# PCB-CMB-5-SHLD-1208.net
KiCad netlist of a schematic drawn in EAGLE
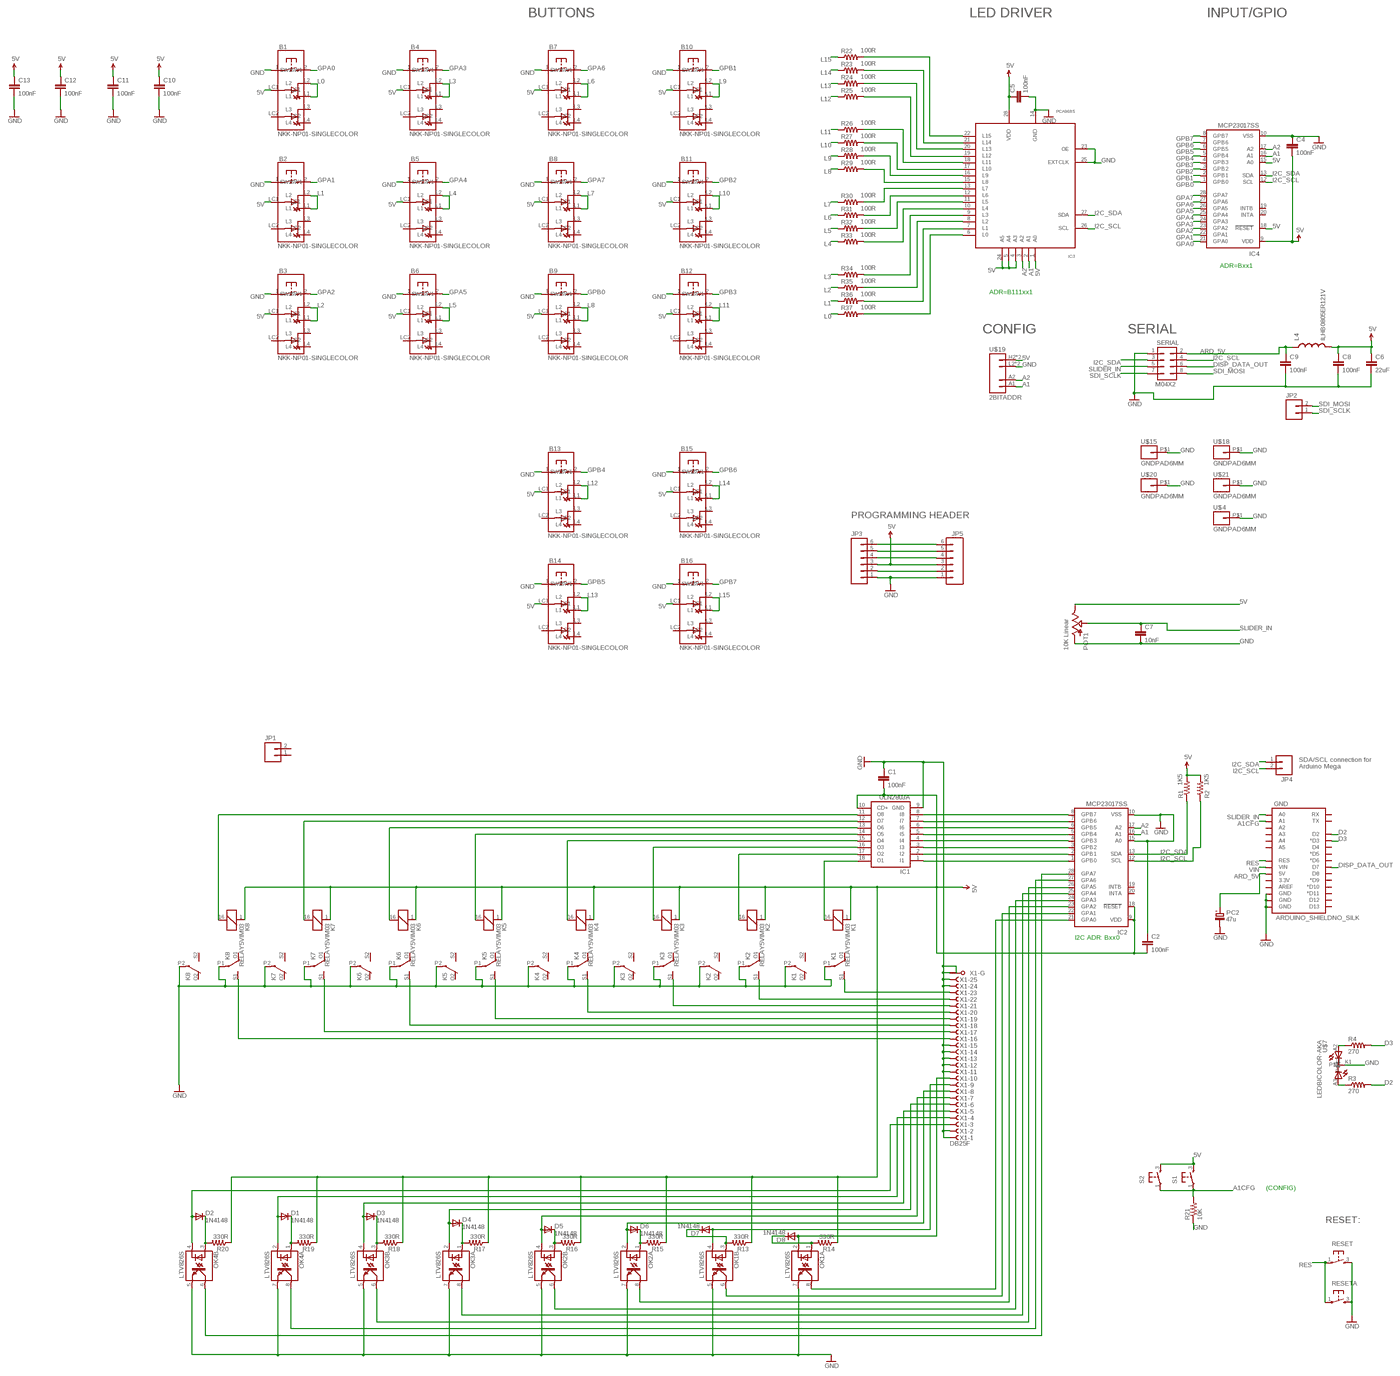
[diagram p0: schematic, sheet 1, overview]
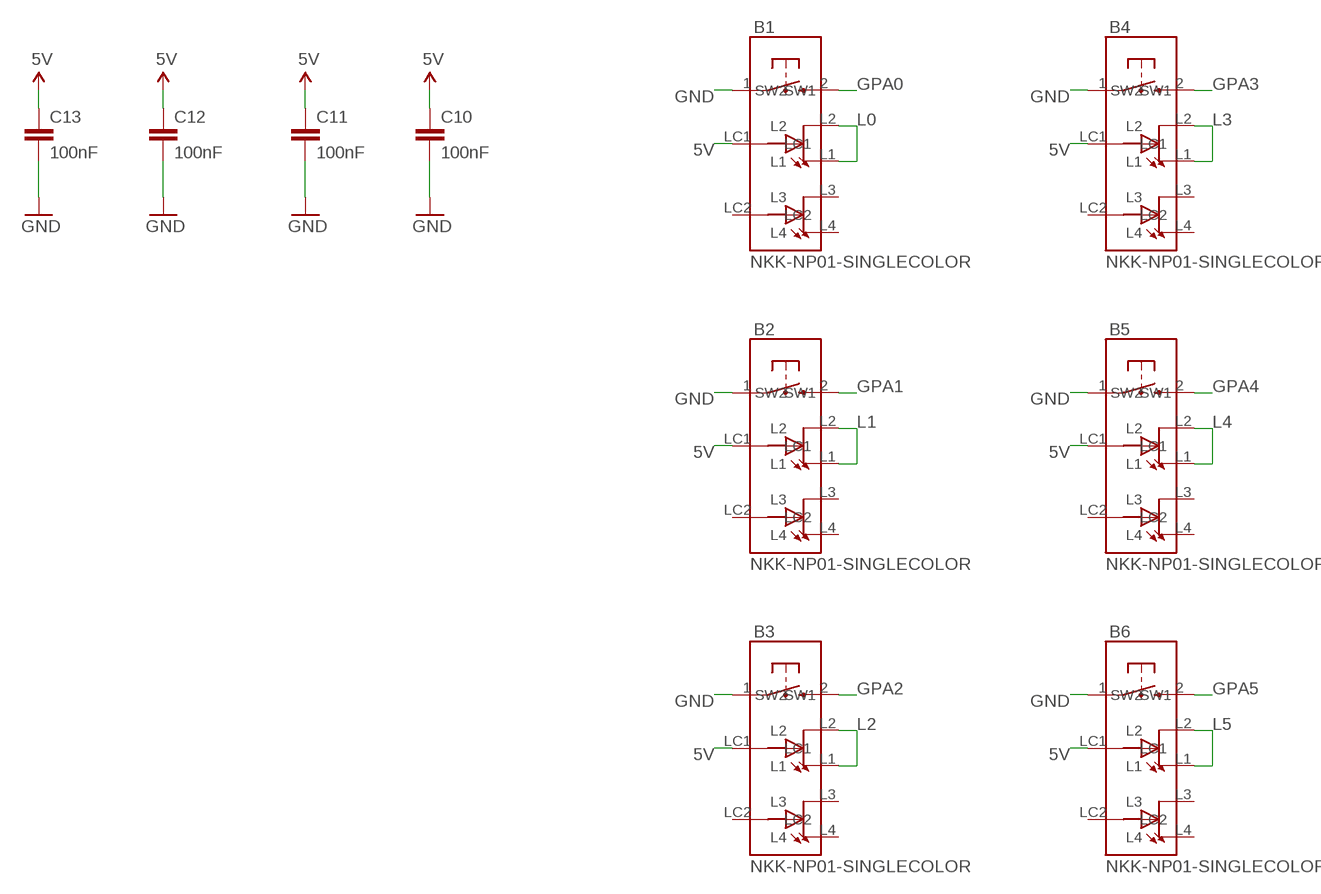
[diagram p1: schematic, sheet 1, part 1 of 4]
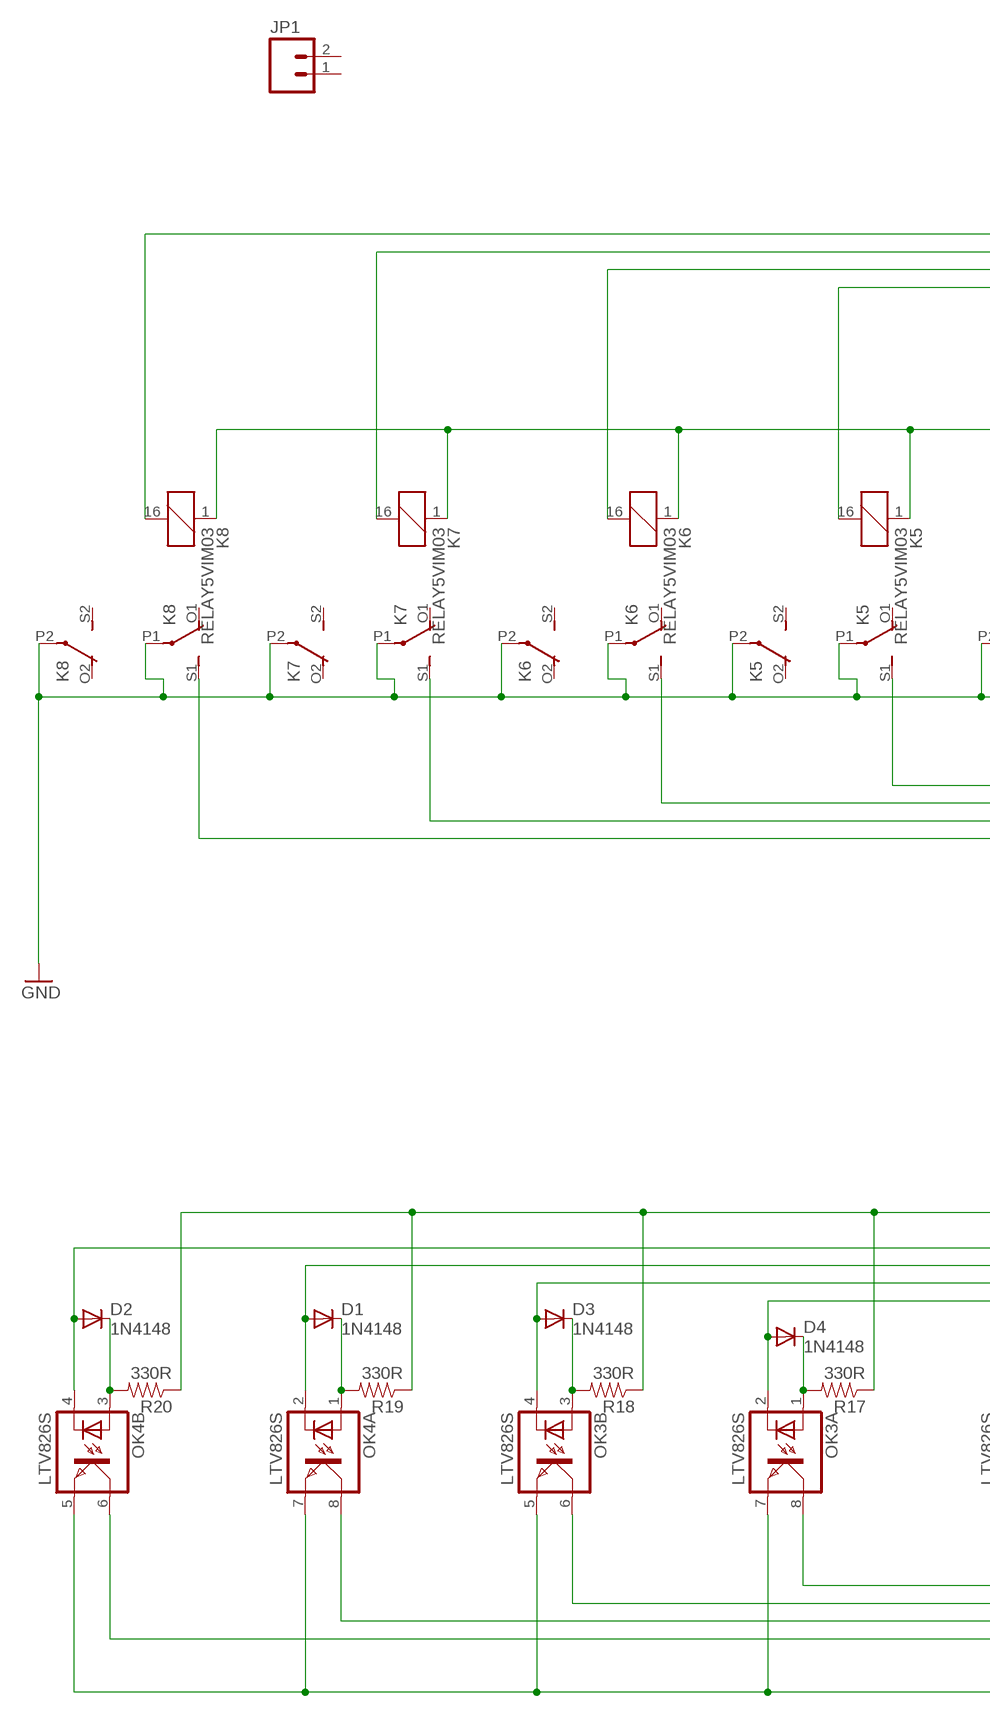
[diagram p2: schematic, sheet 1, part 2 of 4]
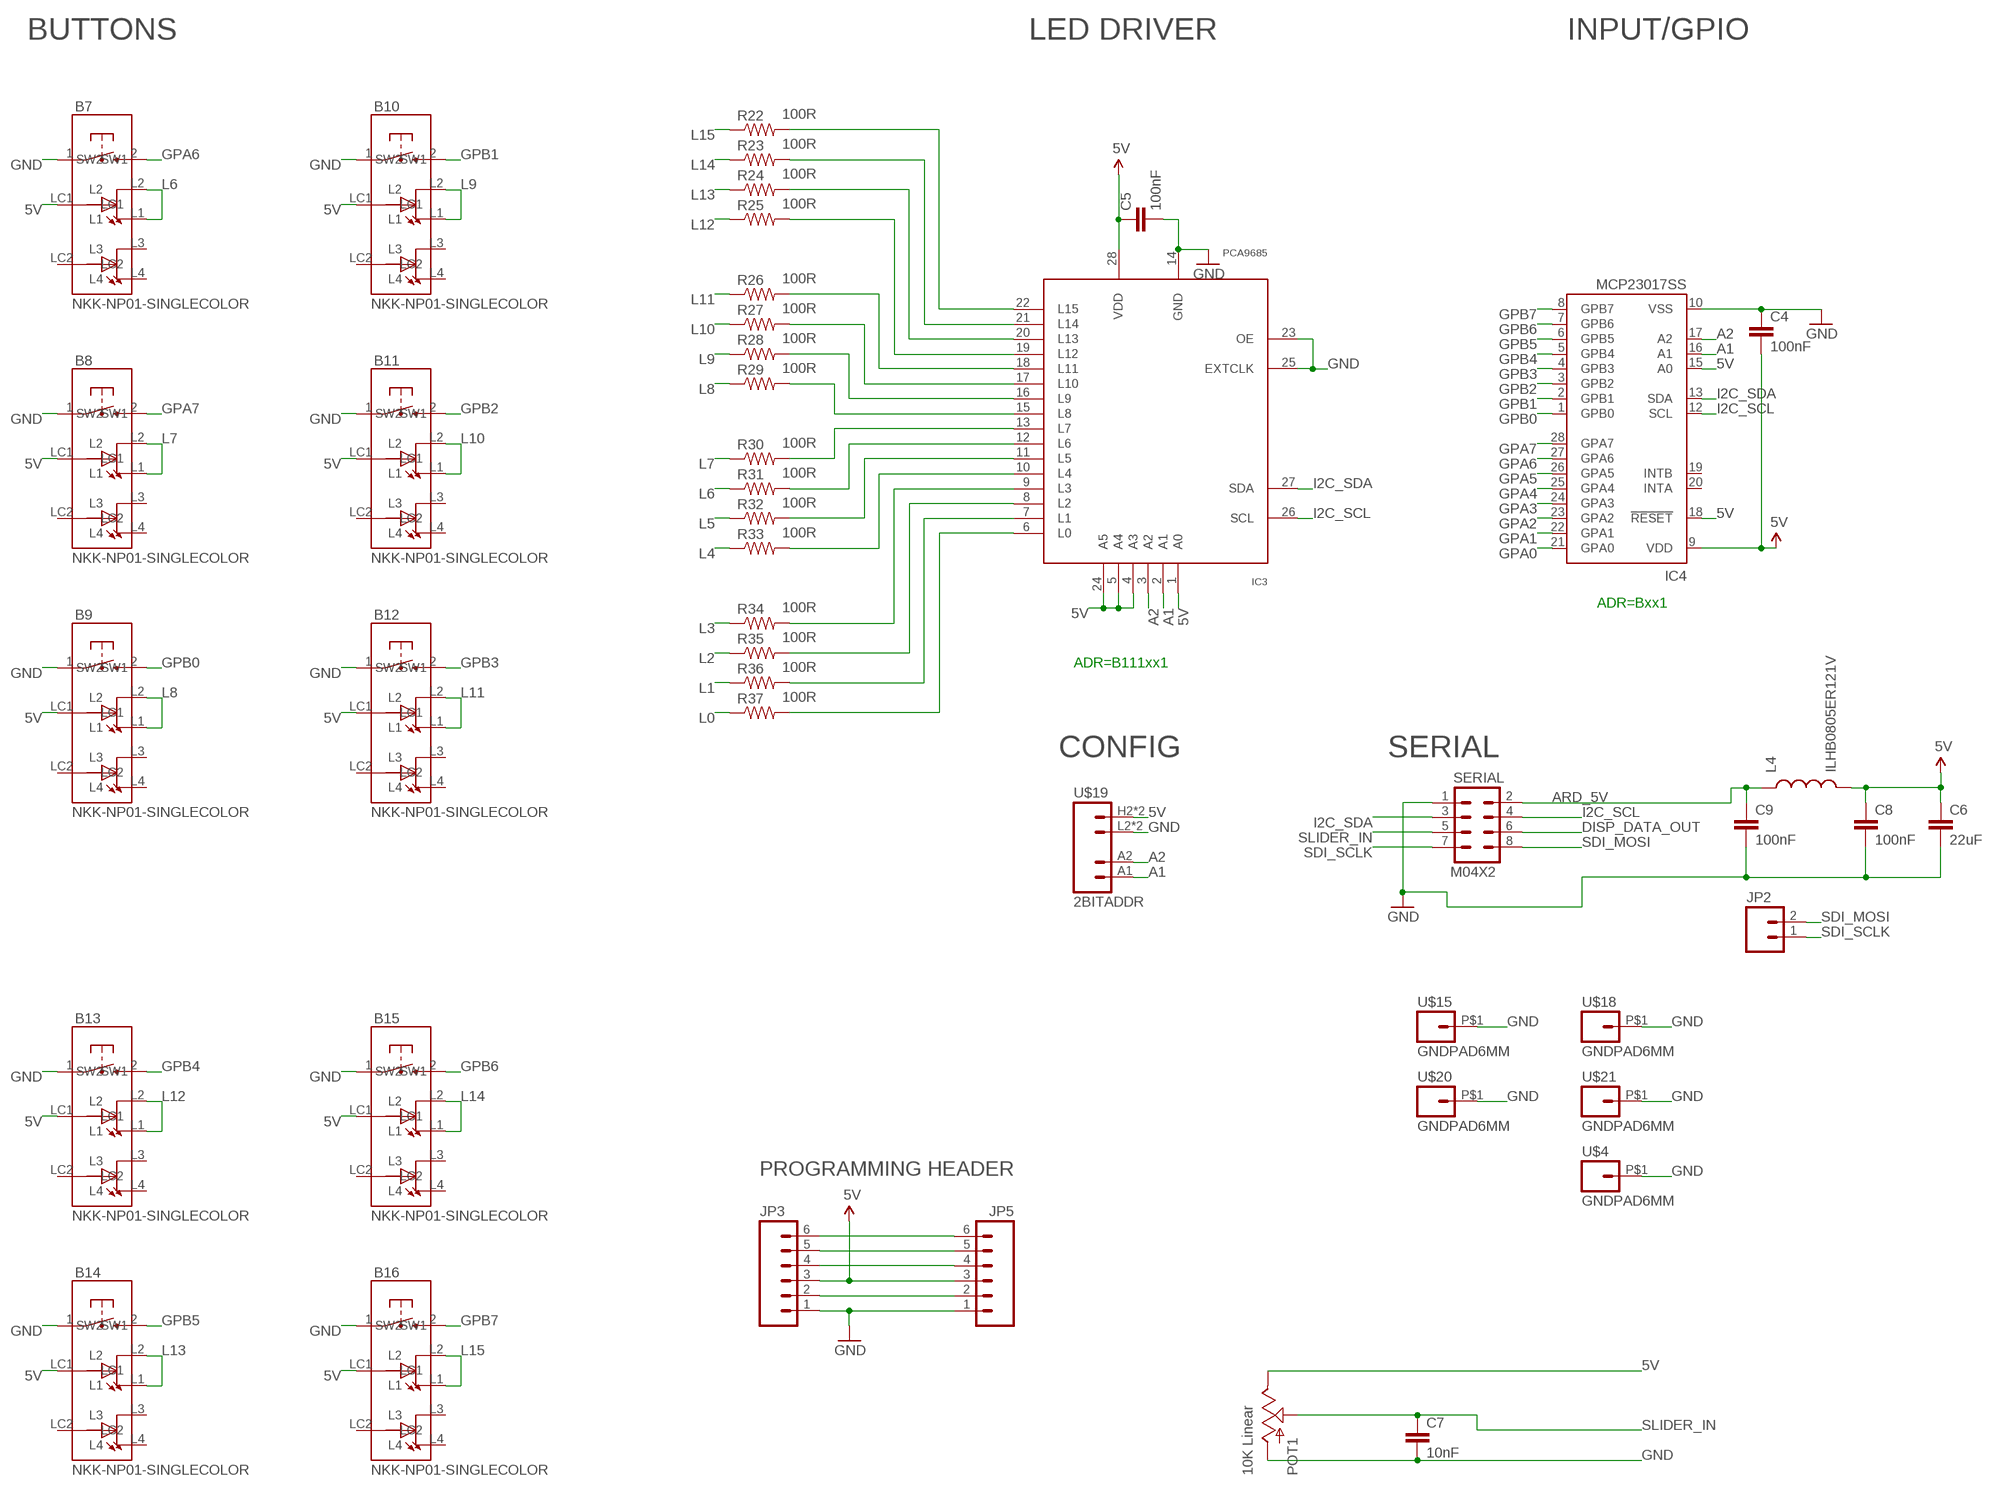
[diagram p3: schematic, sheet 1, part 3 of 4]
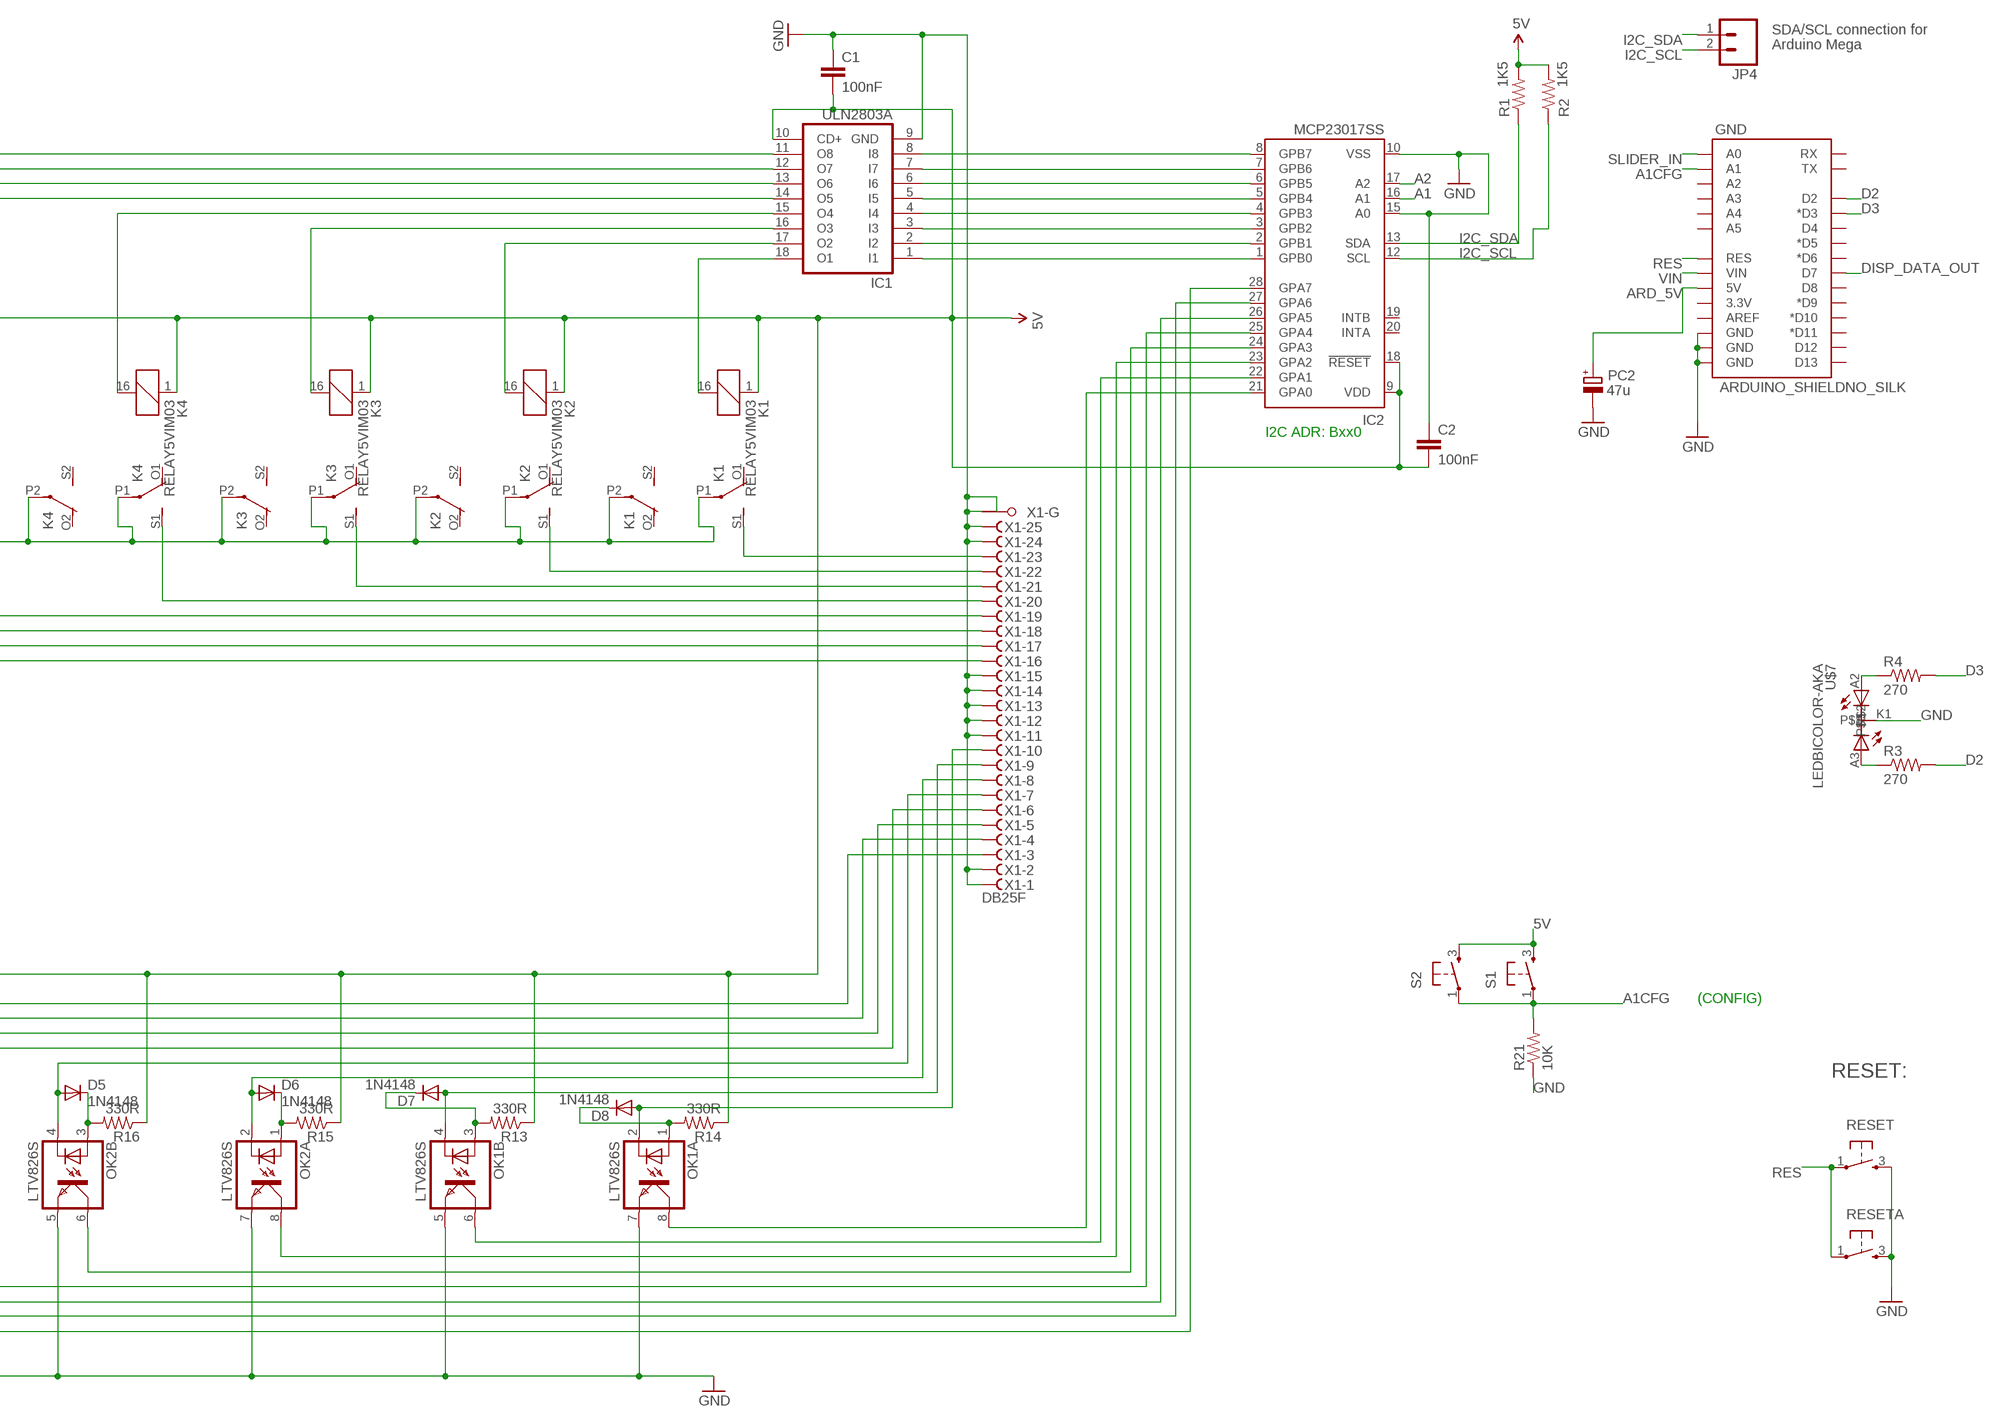
[diagram p4: schematic, sheet 1, part 4 of 4]

(export (version "E")
  (design (tool "Eeschema 10.0.6"))
  (components
    (comp (ref "B1")
      (value "NKK-NP01-SINGLECOLOR")
      (footprint "eagle-import:NKK-NP01")
      (libsource (lib "eagle-import") (part "NKK-NP01-SINGLECOLOR"))
    )
    (comp (ref "B2")
      (value "NKK-NP01-SINGLECOLOR")
      (footprint "eagle-import:NKK-NP01")
      (libsource (lib "eagle-import") (part "NKK-NP01-SINGLECOLOR"))
    )
    (comp (ref "B3")
      (value "NKK-NP01-SINGLECOLOR")
      (footprint "eagle-import:NKK-NP01")
      (libsource (lib "eagle-import") (part "NKK-NP01-SINGLECOLOR"))
    )
    (comp (ref "B4")
      (value "NKK-NP01-SINGLECOLOR")
      (footprint "eagle-import:NKK-NP01")
      (libsource (lib "eagle-import") (part "NKK-NP01-SINGLECOLOR"))
    )
    (comp (ref "B5")
      (value "NKK-NP01-SINGLECOLOR")
      (footprint "eagle-import:NKK-NP01")
      (libsource (lib "eagle-import") (part "NKK-NP01-SINGLECOLOR"))
    )
    (comp (ref "B6")
      (value "NKK-NP01-SINGLECOLOR")
      (footprint "eagle-import:NKK-NP01")
      (libsource (lib "eagle-import") (part "NKK-NP01-SINGLECOLOR"))
    )
    (comp (ref "B7")
      (value "NKK-NP01-SINGLECOLOR")
      (footprint "eagle-import:NKK-NP01")
      (libsource (lib "eagle-import") (part "NKK-NP01-SINGLECOLOR"))
    )
    (comp (ref "B8")
      (value "NKK-NP01-SINGLECOLOR")
      (footprint "eagle-import:NKK-NP01")
      (libsource (lib "eagle-import") (part "NKK-NP01-SINGLECOLOR"))
    )
    (comp (ref "B9")
      (value "NKK-NP01-SINGLECOLOR")
      (footprint "eagle-import:NKK-NP01")
      (libsource (lib "eagle-import") (part "NKK-NP01-SINGLECOLOR"))
    )
    (comp (ref "B10")
      (value "NKK-NP01-SINGLECOLOR")
      (footprint "eagle-import:NKK-NP01")
      (libsource (lib "eagle-import") (part "NKK-NP01-SINGLECOLOR"))
    )
    (comp (ref "B11")
      (value "NKK-NP01-SINGLECOLOR")
      (footprint "eagle-import:NKK-NP01")
      (libsource (lib "eagle-import") (part "NKK-NP01-SINGLECOLOR"))
    )
    (comp (ref "B12")
      (value "NKK-NP01-SINGLECOLOR")
      (footprint "eagle-import:NKK-NP01")
      (libsource (lib "eagle-import") (part "NKK-NP01-SINGLECOLOR"))
    )
    (comp (ref "B13")
      (value "NKK-NP01-SINGLECOLOR")
      (footprint "eagle-import:NKK-NP01")
      (libsource (lib "eagle-import") (part "NKK-NP01-SINGLECOLOR"))
    )
    (comp (ref "B14")
      (value "NKK-NP01-SINGLECOLOR")
      (footprint "eagle-import:NKK-NP01")
      (libsource (lib "eagle-import") (part "NKK-NP01-SINGLECOLOR"))
    )
    (comp (ref "B15")
      (value "NKK-NP01-SINGLECOLOR")
      (footprint "eagle-import:NKK-NP01")
      (libsource (lib "eagle-import") (part "NKK-NP01-SINGLECOLOR"))
    )
    (comp (ref "B16")
      (value "NKK-NP01-SINGLECOLOR")
      (footprint "eagle-import:NKK-NP01")
      (libsource (lib "eagle-import") (part "NKK-NP01-SINGLECOLOR"))
    )
    (comp (ref "C1")
      (value "100nF")
      (footprint "eagle-import:0805")
      (libsource (lib "eagle-import") (part "CAP0805"))
    )
    (comp (ref "C2")
      (value "100nF")
      (footprint "eagle-import:0603-CAP")
      (libsource (lib "eagle-import") (part "CAP0603-CAP"))
    )
    (comp (ref "C4")
      (value "100nF")
      (footprint "eagle-import:0603-CAP")
      (libsource (lib "eagle-import") (part "CAP0603-CAP"))
    )
    (comp (ref "C5")
      (value "100nF")
      (footprint "eagle-import:0603-CAP")
      (libsource (lib "eagle-import") (part "CAP0603-CAP"))
    )
    (comp (ref "C6")
      (value "22uF")
      (footprint "eagle-import:0805")
      (libsource (lib "eagle-import") (part "CAP0805"))
    )
    (comp (ref "C7")
      (value "10nF")
      (footprint "eagle-import:0603-CAP")
      (libsource (lib "eagle-import") (part "CAP0603-CAP"))
    )
    (comp (ref "C8")
      (value "100nF")
      (footprint "eagle-import:0603-CAP")
      (libsource (lib "eagle-import") (part "CAP0603-CAP"))
    )
    (comp (ref "C9")
      (value "100nF")
      (footprint "eagle-import:0603-CAP")
      (libsource (lib "eagle-import") (part "CAP0603-CAP"))
    )
    (comp (ref "C10")
      (value "100nF")
      (footprint "eagle-import:0603-CAP")
      (libsource (lib "eagle-import") (part "CAP0603-CAP"))
    )
    (comp (ref "C11")
      (value "100nF")
      (footprint "eagle-import:0603-CAP")
      (libsource (lib "eagle-import") (part "CAP0603-CAP"))
    )
    (comp (ref "C12")
      (value "100nF")
      (footprint "eagle-import:0603-CAP")
      (libsource (lib "eagle-import") (part "CAP0603-CAP"))
    )
    (comp (ref "C13")
      (value "100nF")
      (footprint "eagle-import:0603-CAP")
      (libsource (lib "eagle-import") (part "CAP0603-CAP"))
    )
    (comp (ref "D1")
      (value "1N4148")
      (footprint "eagle-import:SOD-323")
      (libsource (lib "eagle-import") (part "DIODESOD"))
    )
    (comp (ref "D2")
      (value "1N4148")
      (footprint "eagle-import:SOD-323")
      (libsource (lib "eagle-import") (part "DIODESOD"))
    )
    (comp (ref "D3")
      (value "1N4148")
      (footprint "eagle-import:SOD-323")
      (libsource (lib "eagle-import") (part "DIODESOD"))
    )
    (comp (ref "D4")
      (value "1N4148")
      (footprint "eagle-import:SOD-323")
      (libsource (lib "eagle-import") (part "DIODESOD"))
    )
    (comp (ref "D5")
      (value "1N4148")
      (footprint "eagle-import:SOD-323")
      (libsource (lib "eagle-import") (part "DIODESOD"))
    )
    (comp (ref "D6")
      (value "1N4148")
      (footprint "eagle-import:SOD-323")
      (libsource (lib "eagle-import") (part "DIODESOD"))
    )
    (comp (ref "D7")
      (value "1N4148")
      (footprint "eagle-import:SOD-323")
      (libsource (lib "eagle-import") (part "DIODESOD"))
    )
    (comp (ref "D8")
      (value "1N4148")
      (footprint "eagle-import:SOD-323")
      (libsource (lib "eagle-import") (part "DIODESOD"))
    )
    (comp (ref "GND")
      (value "ARDUINO_SHIELDNO_SILK")
      (footprint "eagle-import:DUEMILANOVE_VIAS")
      (libsource (lib "eagle-import") (part "ARDUINO_SHIELDNO_SILK"))
    )
    (comp (ref "IC1")
      (value "ULN2803A")
      (footprint "eagle-import:SO18W")
      (libsource (lib "eagle-import") (part "ULN2803ASO18W"))
    )
    (comp (ref "IC2")
      (value "MCP23017SS")
      (footprint "eagle-import:SSOP28")
      (fields (field (name "MF") "MICROCHIP") (field (name "MPN") "MCP23017-E/SS"))
      (libsource (lib "eagle-import") (part "MCP23017SS"))
    )
    (comp (ref "IC3")
      (value "PCA9685")
      (footprint "eagle-import:TSSOP28")
      (libsource (lib "eagle-import") (part "PCA9685"))
    )
    (comp (ref "IC4")
      (value "MCP23017SS")
      (footprint "eagle-import:SSOP28")
      (fields
        (field (name "MF") "MICROCHIP")
        (field (name "MPN") "MCP23017-E/SS")
        (field (name "MPN_1") "MCP23017-E/SS")
        (field (name "OC_FARNELL") "1467674")
        (field (name "OC_NEWARK") "31K2960")
      )
      (libsource (lib "eagle-import") (part "MCP23017SS"))
    )
    (comp (ref "JP1")
      (value "M02PTH")
      (footprint "eagle-import:1X02")
      (libsource (lib "eagle-import") (part "M02PTH"))
    )
    (comp (ref "JP2")
      (value "M02PTH")
      (footprint "eagle-import:1X02")
      (libsource (lib "eagle-import") (part "M02PTH"))
    )
    (comp (ref "JP3")
      (value "M06POLAR")
      (footprint "eagle-import:MOLEX-1X6")
      (libsource (lib "eagle-import") (part "M06POLAR"))
    )
    (comp (ref "JP4")
      (value "M02PTH")
      (footprint "eagle-import:1X02")
      (libsource (lib "eagle-import") (part "M02PTH"))
    )
    (comp (ref "JP5")
      (value "M06POLAR")
      (footprint "eagle-import:MOLEX-1X6")
      (libsource (lib "eagle-import") (part "M06POLAR"))
    )
    (comp (ref "K1")
      (value "RELAY5VIM03")
      (footprint "eagle-import:DS2Y")
      (libsource (lib "eagle-import") (part "RELAY5VIM03"))
    )
    (comp (ref "K2")
      (value "RELAY5VIM03")
      (footprint "eagle-import:DS2Y")
      (libsource (lib "eagle-import") (part "RELAY5VIM03"))
    )
    (comp (ref "K3")
      (value "RELAY5VIM03")
      (footprint "eagle-import:DS2Y")
      (libsource (lib "eagle-import") (part "RELAY5VIM03"))
    )
    (comp (ref "K4")
      (value "RELAY5VIM03")
      (footprint "eagle-import:DS2Y")
      (libsource (lib "eagle-import") (part "RELAY5VIM03"))
    )
    (comp (ref "K5")
      (value "RELAY5VIM03")
      (footprint "eagle-import:DS2Y")
      (libsource (lib "eagle-import") (part "RELAY5VIM03"))
    )
    (comp (ref "K6")
      (value "RELAY5VIM03")
      (footprint "eagle-import:DS2Y")
      (libsource (lib "eagle-import") (part "RELAY5VIM03"))
    )
    (comp (ref "K7")
      (value "RELAY5VIM03")
      (footprint "eagle-import:DS2Y")
      (libsource (lib "eagle-import") (part "RELAY5VIM03"))
    )
    (comp (ref "K8")
      (value "RELAY5VIM03")
      (footprint "eagle-import:DS2Y")
      (libsource (lib "eagle-import") (part "RELAY5VIM03"))
    )
    (comp (ref "L4")
      (value "ILHB0805ER121V")
      (footprint "eagle-import:0805")
      (libsource (lib "eagle-import") (part "INDUCTOR0805"))
    )
    (comp (ref "OK1")
      (value "LTV826S")
      (footprint "eagle-import:DIL8-SMD")
      (libsource (lib "eagle-import") (part "LTV826S"))
    )
    (comp (ref "OK2")
      (value "LTV826S")
      (footprint "eagle-import:DIL8-SMD")
      (libsource (lib "eagle-import") (part "LTV826S"))
    )
    (comp (ref "OK3")
      (value "LTV826S")
      (footprint "eagle-import:DIL8-SMD")
      (libsource (lib "eagle-import") (part "LTV826S"))
    )
    (comp (ref "OK4")
      (value "LTV826S")
      (footprint "eagle-import:DIL8-SMD")
      (libsource (lib "eagle-import") (part "LTV826S"))
    )
    (comp (ref "PC2")
      (value "47u")
      (footprint "eagle-import:PANASONIC_D")
      (libsource (lib "eagle-import") (part "CPOL-EUD"))
    )
    (comp (ref "POT1")
      (value "10K Linear")
      (footprint "eagle-import:SLIDER20")
      (libsource (lib "eagle-import") (part "SLIDER20"))
    )
    (comp (ref "R1")
      (value "1K5")
      (footprint "eagle-import:0603-RES")
      (libsource (lib "eagle-import") (part "RESISTOR0603-RES"))
    )
    (comp (ref "R2")
      (value "1K5")
      (footprint "eagle-import:0603-RES")
      (libsource (lib "eagle-import") (part "RESISTOR0603-RES"))
    )
    (comp (ref "R3")
      (value "270")
      (footprint "eagle-import:0603-RES")
      (libsource (lib "eagle-import") (part "RESISTOR0603-RES"))
    )
    (comp (ref "R4")
      (value "270")
      (footprint "eagle-import:0603-RES")
      (libsource (lib "eagle-import") (part "RESISTOR0603-RES"))
    )
    (comp (ref "R13")
      (value "330R")
      (footprint "eagle-import:0603-RES")
      (libsource (lib "eagle-import") (part "RESISTOR0603-RES"))
    )
    (comp (ref "R14")
      (value "330R")
      (footprint "eagle-import:0603-RES")
      (libsource (lib "eagle-import") (part "RESISTOR0603-RES"))
    )
    (comp (ref "R15")
      (value "330R")
      (footprint "eagle-import:0603-RES")
      (libsource (lib "eagle-import") (part "RESISTOR0603-RES"))
    )
    (comp (ref "R16")
      (value "330R")
      (footprint "eagle-import:0603-RES")
      (libsource (lib "eagle-import") (part "RESISTOR0603-RES"))
    )
    (comp (ref "R17")
      (value "330R")
      (footprint "eagle-import:0603-RES")
      (libsource (lib "eagle-import") (part "RESISTOR0603-RES"))
    )
    (comp (ref "R18")
      (value "330R")
      (footprint "eagle-import:0603-RES")
      (libsource (lib "eagle-import") (part "RESISTOR0603-RES"))
    )
    (comp (ref "R19")
      (value "330R")
      (footprint "eagle-import:0603-RES")
      (libsource (lib "eagle-import") (part "RESISTOR0603-RES"))
    )
    (comp (ref "R20")
      (value "330R")
      (footprint "eagle-import:0603-RES")
      (libsource (lib "eagle-import") (part "RESISTOR0603-RES"))
    )
    (comp (ref "R21")
      (value "10K")
      (footprint "eagle-import:0603-RES")
      (libsource (lib "eagle-import") (part "RESISTOR0603-RES"))
    )
    (comp (ref "R22")
      (value "100R")
      (footprint "eagle-import:1206")
      (libsource (lib "eagle-import") (part "RESISTOR1206"))
    )
    (comp (ref "R23")
      (value "100R")
      (footprint "eagle-import:1206")
      (libsource (lib "eagle-import") (part "RESISTOR1206"))
    )
    (comp (ref "R24")
      (value "100R")
      (footprint "eagle-import:1206")
      (libsource (lib "eagle-import") (part "RESISTOR1206"))
    )
    (comp (ref "R25")
      (value "100R")
      (footprint "eagle-import:1206")
      (libsource (lib "eagle-import") (part "RESISTOR1206"))
    )
    (comp (ref "R26")
      (value "100R")
      (footprint "eagle-import:1206")
      (libsource (lib "eagle-import") (part "RESISTOR1206"))
    )
    (comp (ref "R27")
      (value "100R")
      (footprint "eagle-import:1206")
      (libsource (lib "eagle-import") (part "RESISTOR1206"))
    )
    (comp (ref "R28")
      (value "100R")
      (footprint "eagle-import:1206")
      (libsource (lib "eagle-import") (part "RESISTOR1206"))
    )
    (comp (ref "R29")
      (value "100R")
      (footprint "eagle-import:1206")
      (libsource (lib "eagle-import") (part "RESISTOR1206"))
    )
    (comp (ref "R30")
      (value "100R")
      (footprint "eagle-import:1206")
      (libsource (lib "eagle-import") (part "RESISTOR1206"))
    )
    (comp (ref "R31")
      (value "100R")
      (footprint "eagle-import:1206")
      (libsource (lib "eagle-import") (part "RESISTOR1206"))
    )
    (comp (ref "R32")
      (value "100R")
      (footprint "eagle-import:1206")
      (libsource (lib "eagle-import") (part "RESISTOR1206"))
    )
    (comp (ref "R33")
      (value "100R")
      (footprint "eagle-import:1206")
      (libsource (lib "eagle-import") (part "RESISTOR1206"))
    )
    (comp (ref "R34")
      (value "100R")
      (footprint "eagle-import:1206")
      (libsource (lib "eagle-import") (part "RESISTOR1206"))
    )
    (comp (ref "R35")
      (value "100R")
      (footprint "eagle-import:1206")
      (libsource (lib "eagle-import") (part "RESISTOR1206"))
    )
    (comp (ref "R36")
      (value "100R")
      (footprint "eagle-import:1206")
      (libsource (lib "eagle-import") (part "RESISTOR1206"))
    )
    (comp (ref "R37")
      (value "100R")
      (footprint "eagle-import:1206")
      (libsource (lib "eagle-import") (part "RESISTOR1206"))
    )
    (comp (ref "RESET")
      (value "TAC_SWITCH")
      (footprint "eagle-import:PUSHBUTTON")
      (libsource (lib "eagle-import") (part "TAC_SWITCH"))
    )
    (comp (ref "RESETA")
      (value "TAC_SWITCH")
      (footprint "eagle-import:PUSHBUTTON")
      (libsource (lib "eagle-import") (part "TAC_SWITCH"))
    )
    (comp (ref "S1")
      (value "TAC_SWITCH")
      (footprint "eagle-import:PUSHBUTTON")
      (libsource (lib "eagle-import") (part "TAC_SWITCH"))
    )
    (comp (ref "S2")
      (value "TAC_SWITCH")
      (footprint "eagle-import:PUSHBUTTON")
      (libsource (lib "eagle-import") (part "TAC_SWITCH"))
    )
    (comp (ref "SERIAL")
      (value "M04X2")
      (footprint "eagle-import:2X4")
      (libsource (lib "eagle-import") (part "M04X2"))
    )
    (comp (ref "U$4")
      (value "GNDPAD6MM")
      (footprint "eagle-import:3.2MMPAD6MM")
      (libsource (lib "eagle-import") (part "GNDPAD6MM"))
    )
    (comp (ref "U$7")
      (value "LEDBICOLOR-AKA")
      (footprint "eagle-import:LED5MM-BICOLOR")
      (libsource (lib "eagle-import") (part "LEDBICOLOR-AKA"))
    )
    (comp (ref "U$15")
      (value "GNDPAD6MM")
      (footprint "eagle-import:3.2MMPAD6MM")
      (libsource (lib "eagle-import") (part "GNDPAD6MM"))
    )
    (comp (ref "U$18")
      (value "GNDPAD6MM")
      (footprint "eagle-import:3.2MMPAD6MM")
      (libsource (lib "eagle-import") (part "GNDPAD6MM"))
    )
    (comp (ref "U$19")
      (value "2BITADDR")
      (footprint "eagle-import:2BITADDR")
      (libsource (lib "eagle-import") (part "2BITADDR"))
    )
    (comp (ref "U$20")
      (value "GNDPAD6MM")
      (footprint "eagle-import:3.2MMPAD6MM")
      (libsource (lib "eagle-import") (part "GNDPAD6MM"))
    )
    (comp (ref "U$21")
      (value "GNDPAD6MM")
      (footprint "eagle-import:3.2MMPAD6MM")
      (libsource (lib "eagle-import") (part "GNDPAD6MM"))
    )
    (comp (ref "X1")
      (value "DB25F")
      (footprint "eagle-import:F25HP")
      (libsource (lib "eagle-import") (part "F25HPS"))
    )
  )
  (nets
    (net (code "1") (name "5V") (class "Default")
      (node (ref "B1") (pin "LC1") (pinfunction "LC1_LC1") (pintype "bidirectional"))
      (node (ref "B10") (pin "LC1") (pinfunction "LC1_LC1") (pintype "bidirectional"))
      (node (ref "B11") (pin "LC1") (pinfunction "LC1_LC1") (pintype "bidirectional"))
      (node (ref "B12") (pin "LC1") (pinfunction "LC1_LC1") (pintype "bidirectional"))
      (node (ref "B13") (pin "LC1") (pinfunction "LC1_LC1") (pintype "bidirectional"))
      (node (ref "B14") (pin "LC1") (pinfunction "LC1_LC1") (pintype "bidirectional"))
      (node (ref "B15") (pin "LC1") (pinfunction "LC1_LC1") (pintype "bidirectional"))
      (node (ref "B16") (pin "LC1") (pinfunction "LC1_LC1") (pintype "bidirectional"))
      (node (ref "B2") (pin "LC1") (pinfunction "LC1_LC1") (pintype "bidirectional"))
      (node (ref "B3") (pin "LC1") (pinfunction "LC1_LC1") (pintype "bidirectional"))
      (node (ref "B4") (pin "LC1") (pinfunction "LC1_LC1") (pintype "bidirectional"))
      (node (ref "B5") (pin "LC1") (pinfunction "LC1_LC1") (pintype "bidirectional"))
      (node (ref "B6") (pin "LC1") (pinfunction "LC1_LC1") (pintype "bidirectional"))
      (node (ref "B7") (pin "LC1") (pinfunction "LC1_LC1") (pintype "bidirectional"))
      (node (ref "B8") (pin "LC1") (pinfunction "LC1_LC1") (pintype "bidirectional"))
      (node (ref "B9") (pin "LC1") (pinfunction "LC1_LC1") (pintype "bidirectional"))
      (node (ref "C1") (pin "2") (pinfunction "2_2") (pintype "passive"))
      (node (ref "C10") (pin "1") (pinfunction "1_1") (pintype "passive"))
      (node (ref "C11") (pin "1") (pinfunction "1_1") (pintype "passive"))
      (node (ref "C12") (pin "1") (pinfunction "1_1") (pintype "passive"))
      (node (ref "C13") (pin "1") (pinfunction "1_1") (pintype "passive"))
      (node (ref "C2") (pin "2") (pinfunction "2_2") (pintype "passive"))
      (node (ref "C4") (pin "2") (pinfunction "2_2") (pintype "passive"))
      (node (ref "C5") (pin "1") (pinfunction "1_1") (pintype "passive"))
      (node (ref "C6") (pin "1") (pinfunction "1_1") (pintype "passive"))
      (node (ref "C8") (pin "1") (pinfunction "1_1") (pintype "passive"))
      (node (ref "IC1") (pin "10") (pinfunction "CD+_10") (pintype "passive"))
      (node (ref "IC2") (pin "18") (pinfunction "~{RESET}_18") (pintype "input"))
      (node (ref "IC2") (pin "9") (pinfunction "VDD_9") (pintype "power_in"))
      (node (ref "IC3") (pin "1") (pinfunction "A0_1") (pintype "input"))
      (node (ref "IC3") (pin "24") (pinfunction "A5_24") (pintype "input"))
      (node (ref "IC3") (pin "28") (pinfunction "VDD_28") (pintype "power_in"))
      (node (ref "IC3") (pin "4") (pinfunction "A3_4") (pintype "input"))
      (node (ref "IC3") (pin "5") (pinfunction "A4_5") (pintype "input"))
      (node (ref "IC4") (pin "15") (pinfunction "A0_15") (pintype "input"))
      (node (ref "IC4") (pin "18") (pinfunction "~{RESET}_18") (pintype "input"))
      (node (ref "IC4") (pin "9") (pinfunction "VDD_9") (pintype "power_in"))
      (node (ref "JP3") (pin "3") (pinfunction "3_3") (pintype "passive"))
      (node (ref "JP5") (pin "3") (pinfunction "3_3") (pintype "passive"))
      (node (ref "K1") (pin "1") (pinfunction "1_1") (pintype "passive"))
      (node (ref "K2") (pin "1") (pinfunction "1_1") (pintype "passive"))
      (node (ref "K3") (pin "1") (pinfunction "1_1") (pintype "passive"))
      (node (ref "K4") (pin "1") (pinfunction "1_1") (pintype "passive"))
      (node (ref "K5") (pin "1") (pinfunction "1_1") (pintype "passive"))
      (node (ref "K6") (pin "1") (pinfunction "1_1") (pintype "passive"))
      (node (ref "K7") (pin "1") (pinfunction "1_1") (pintype "passive"))
      (node (ref "K8") (pin "1") (pinfunction "1_1") (pintype "passive"))
      (node (ref "L4") (pin "2") (pinfunction "2_2") (pintype "passive"))
      (node (ref "POT1") (pin "1") (pinfunction "E_1") (pintype "passive"))
      (node (ref "R1") (pin "2") (pinfunction "2_2") (pintype "passive"))
      (node (ref "R13") (pin "1") (pinfunction "1_1") (pintype "passive"))
      (node (ref "R14") (pin "1") (pinfunction "1_1") (pintype "passive"))
      (node (ref "R15") (pin "1") (pinfunction "1_1") (pintype "passive"))
      (node (ref "R16") (pin "1") (pinfunction "1_1") (pintype "passive"))
      (node (ref "R17") (pin "1") (pinfunction "1_1") (pintype "passive"))
      (node (ref "R18") (pin "1") (pinfunction "1_1") (pintype "passive"))
      (node (ref "R19") (pin "1") (pinfunction "1_1") (pintype "passive"))
      (node (ref "R2") (pin "2") (pinfunction "2_2") (pintype "passive"))
      (node (ref "R20") (pin "1") (pinfunction "1_1") (pintype "passive"))
      (node (ref "S1") (pin "3") (pinfunction "3_3") (pintype "passive"))
      (node (ref "S2") (pin "3") (pinfunction "3_3") (pintype "passive"))
      (node (ref "U$19") (pin "H2") (pinfunction "VCC_H2") (pintype "passive"))
      (node (ref "U$19") (pin "H3") (pinfunction "VCC_H3") (pintype "passive"))
    )
    (net (code "2") (name "A1") (class "Default")
      (node (ref "IC2") (pin "16") (pinfunction "A1_16") (pintype "input"))
      (node (ref "IC3") (pin "2") (pinfunction "A1_2") (pintype "input"))
      (node (ref "IC4") (pin "16") (pinfunction "A1_16") (pintype "input"))
      (node (ref "U$19") (pin "A1") (pinfunction "A1_A1") (pintype "passive"))
    )
    (net (code "3") (name "A1CFG") (class "Default")
      (node (ref "GND") (pin "A1") (pinfunction "A1_A1") (pintype "bidirectional"))
      (node (ref "R21") (pin "2") (pinfunction "2_2") (pintype "passive"))
      (node (ref "S1") (pin "1") (pinfunction "1_1") (pintype "passive"))
      (node (ref "S2") (pin "1") (pinfunction "1_1") (pintype "passive"))
    )
    (net (code "4") (name "A2") (class "Default")
      (node (ref "IC2") (pin "17") (pinfunction "A2_17") (pintype "input"))
      (node (ref "IC3") (pin "3") (pinfunction "A2_3") (pintype "input"))
      (node (ref "IC4") (pin "17") (pinfunction "A2_17") (pintype "input"))
      (node (ref "U$19") (pin "A2") (pinfunction "A2_A2") (pintype "passive"))
    )
    (net (code "5") (name "ARD_5V") (class "Default")
      (node (ref "C9") (pin "1") (pinfunction "1_1") (pintype "passive"))
      (node (ref "GND") (pin "5V") (pinfunction "5V_5V") (pintype "bidirectional"))
      (node (ref "L4") (pin "1") (pinfunction "1_1") (pintype "passive"))
      (node (ref "PC2") (pin "+") (pinfunction "+_+") (pintype "passive"))
      (node (ref "SERIAL") (pin "2") (pinfunction "2_2") (pintype "passive"))
    )
    (net (code "6") (name "D2") (class "Default")
      (node (ref "GND") (pin "D2") (pinfunction "D2_D2") (pintype "bidirectional"))
      (node (ref "R3") (pin "2") (pinfunction "2_2") (pintype "passive"))
    )
    (net (code "7") (name "D3") (class "Default")
      (node (ref "GND") (pin "D3") (pinfunction "*D3_D3") (pintype "bidirectional"))
      (node (ref "R4") (pin "2") (pinfunction "2_2") (pintype "passive"))
    )
    (net (code "8") (name "DISP_DATA_OUT") (class "Default")
      (node (ref "GND") (pin "D7") (pinfunction "D7_D7") (pintype "bidirectional"))
      (node (ref "SERIAL") (pin "6") (pinfunction "6_6") (pintype "passive"))
    )
    (net (code "9") (name "GND") (class "Default")
      (node (ref "B1") (pin "1") (pinfunction "SW1_1") (pintype "bidirectional"))
      (node (ref "B10") (pin "1") (pinfunction "SW1_1") (pintype "bidirectional"))
      (node (ref "B11") (pin "1") (pinfunction "SW1_1") (pintype "bidirectional"))
      (node (ref "B12") (pin "1") (pinfunction "SW1_1") (pintype "bidirectional"))
      (node (ref "B13") (pin "1") (pinfunction "SW1_1") (pintype "bidirectional"))
      (node (ref "B14") (pin "1") (pinfunction "SW1_1") (pintype "bidirectional"))
      (node (ref "B15") (pin "1") (pinfunction "SW1_1") (pintype "bidirectional"))
      (node (ref "B16") (pin "1") (pinfunction "SW1_1") (pintype "bidirectional"))
      (node (ref "B2") (pin "1") (pinfunction "SW1_1") (pintype "bidirectional"))
      (node (ref "B3") (pin "1") (pinfunction "SW1_1") (pintype "bidirectional"))
      (node (ref "B4") (pin "1") (pinfunction "SW1_1") (pintype "bidirectional"))
      (node (ref "B5") (pin "1") (pinfunction "SW1_1") (pintype "bidirectional"))
      (node (ref "B6") (pin "1") (pinfunction "SW1_1") (pintype "bidirectional"))
      (node (ref "B7") (pin "1") (pinfunction "SW1_1") (pintype "bidirectional"))
      (node (ref "B8") (pin "1") (pinfunction "SW1_1") (pintype "bidirectional"))
      (node (ref "B9") (pin "1") (pinfunction "SW1_1") (pintype "bidirectional"))
      (node (ref "C1") (pin "1") (pinfunction "1_1") (pintype "passive"))
      (node (ref "C10") (pin "2") (pinfunction "2_2") (pintype "passive"))
      (node (ref "C11") (pin "2") (pinfunction "2_2") (pintype "passive"))
      (node (ref "C12") (pin "2") (pinfunction "2_2") (pintype "passive"))
      (node (ref "C13") (pin "2") (pinfunction "2_2") (pintype "passive"))
      (node (ref "C2") (pin "1") (pinfunction "1_1") (pintype "passive"))
      (node (ref "C4") (pin "1") (pinfunction "1_1") (pintype "passive"))
      (node (ref "C5") (pin "2") (pinfunction "2_2") (pintype "passive"))
      (node (ref "C6") (pin "2") (pinfunction "2_2") (pintype "passive"))
      (node (ref "C7") (pin "2") (pinfunction "2_2") (pintype "passive"))
      (node (ref "C8") (pin "2") (pinfunction "2_2") (pintype "passive"))
      (node (ref "C9") (pin "2") (pinfunction "2_2") (pintype "passive"))
      (node (ref "GND") (pin "GND@0") (pinfunction "GND_GND@0") (pintype "bidirectional"))
      (node (ref "GND") (pin "GND@1") (pinfunction "GND_GND@1") (pintype "bidirectional"))
      (node (ref "GND") (pin "GND@2") (pinfunction "GND_GND@2") (pintype "bidirectional"))
      (node (ref "IC1") (pin "9") (pinfunction "GND_9") (pintype "power_in"))
      (node (ref "IC2") (pin "10") (pinfunction "VSS_10") (pintype "power_in"))
      (node (ref "IC2") (pin "15") (pinfunction "A0_15") (pintype "input"))
      (node (ref "IC3") (pin "14") (pinfunction "GND_14") (pintype "power_in"))
      (node (ref "IC3") (pin "23") (pinfunction "OE_23") (pintype "input"))
      (node (ref "IC3") (pin "25") (pinfunction "EXTCLK_25") (pintype "input"))
      (node (ref "IC4") (pin "10") (pinfunction "VSS_10") (pintype "power_in"))
      (node (ref "JP3") (pin "1") (pinfunction "1_1") (pintype "passive"))
      (node (ref "JP5") (pin "1") (pinfunction "1_1") (pintype "passive"))
      (node (ref "K1") (pin "P1") (pinfunction "P_P1") (pintype "passive"))
      (node (ref "K1") (pin "P2") (pinfunction "P_P2") (pintype "passive"))
      (node (ref "K2") (pin "P1") (pinfunction "P_P1") (pintype "passive"))
      (node (ref "K2") (pin "P2") (pinfunction "P_P2") (pintype "passive"))
      (node (ref "K3") (pin "P1") (pinfunction "P_P1") (pintype "passive"))
      (node (ref "K3") (pin "P2") (pinfunction "P_P2") (pintype "passive"))
      (node (ref "K4") (pin "P1") (pinfunction "P_P1") (pintype "passive"))
      (node (ref "K4") (pin "P2") (pinfunction "P_P2") (pintype "passive"))
      (node (ref "K5") (pin "P1") (pinfunction "P_P1") (pintype "passive"))
      (node (ref "K5") (pin "P2") (pinfunction "P_P2") (pintype "passive"))
      (node (ref "K6") (pin "P1") (pinfunction "P_P1") (pintype "passive"))
      (node (ref "K6") (pin "P2") (pinfunction "P_P2") (pintype "passive"))
      (node (ref "K7") (pin "P1") (pinfunction "P_P1") (pintype "passive"))
      (node (ref "K7") (pin "P2") (pinfunction "P_P2") (pintype "passive"))
      (node (ref "K8") (pin "P1") (pinfunction "P_P1") (pintype "passive"))
      (node (ref "K8") (pin "P2") (pinfunction "P_P2") (pintype "passive"))
      (node (ref "OK1") (pin "5") (pinfunction "EMIT_5") (pintype "passive"))
      (node (ref "OK1") (pin "7") (pinfunction "EMIT_7") (pintype "passive"))
      (node (ref "OK2") (pin "5") (pinfunction "EMIT_5") (pintype "passive"))
      (node (ref "OK2") (pin "7") (pinfunction "EMIT_7") (pintype "passive"))
      (node (ref "OK3") (pin "5") (pinfunction "EMIT_5") (pintype "passive"))
      (node (ref "OK3") (pin "7") (pinfunction "EMIT_7") (pintype "passive"))
      (node (ref "OK4") (pin "5") (pinfunction "EMIT_5") (pintype "passive"))
      (node (ref "OK4") (pin "7") (pinfunction "EMIT_7") (pintype "passive"))
      (node (ref "PC2") (pin "-") (pinfunction "-_-") (pintype "passive"))
      (node (ref "POT1") (pin "3") (pinfunction "A_3") (pintype "passive"))
      (node (ref "R21") (pin "1") (pinfunction "1_1") (pintype "passive"))
      (node (ref "RESET") (pin "3") (pinfunction "3_3") (pintype "passive"))
      (node (ref "RESETA") (pin "3") (pinfunction "3_3") (pintype "passive"))
      (node (ref "SERIAL") (pin "1") (pinfunction "1_1") (pintype "passive"))
      (node (ref "U$15") (pin "P$1") (pinfunction "1_P$1") (pintype "passive"))
      (node (ref "U$18") (pin "P$1") (pinfunction "1_P$1") (pintype "passive"))
      (node (ref "U$19") (pin "L2") (pinfunction "GND_L2") (pintype "passive"))
      (node (ref "U$19") (pin "L3") (pinfunction "GND_L3") (pintype "passive"))
      (node (ref "U$20") (pin "P$1") (pinfunction "1_P$1") (pintype "passive"))
      (node (ref "U$21") (pin "P$1") (pinfunction "1_P$1") (pintype "passive"))
      (node (ref "U$4") (pin "P$1") (pinfunction "1_P$1") (pintype "passive"))
      (node (ref "U$7") (pin "K1") (pinfunction "P$1_K1") (pintype "bidirectional"))
      (node (ref "X1") (pin "1") (pinfunction "F_1") (pintype "passive"))
      (node (ref "X1") (pin "11") (pinfunction "F_11") (pintype "passive"))
      (node (ref "X1") (pin "12") (pinfunction "F_12") (pintype "passive"))
      (node (ref "X1") (pin "13") (pinfunction "F_13") (pintype "passive"))
      (node (ref "X1") (pin "14") (pinfunction "F_14") (pintype "passive"))
      (node (ref "X1") (pin "15") (pinfunction "F_15") (pintype "passive"))
      (node (ref "X1") (pin "2") (pinfunction "F_2") (pintype "passive"))
      (node (ref "X1") (pin "24") (pinfunction "F_24") (pintype "passive"))
      (node (ref "X1") (pin "25") (pinfunction "F_25") (pintype "passive"))
      (node (ref "X1") (pin "G1") (pinfunction "G1_G1") (pintype "passive"))
      (node (ref "X1") (pin "G2") (pinfunction "G2_G2") (pintype "passive"))
    )
    (net (code "10") (name "GPA0") (class "Default")
      (node (ref "B1") (pin "2") (pinfunction "SW2_2") (pintype "bidirectional"))
      (node (ref "IC4") (pin "21") (pinfunction "GPA0_21") (pintype "bidirectional"))
    )
    (net (code "11") (name "GPA1") (class "Default")
      (node (ref "B2") (pin "2") (pinfunction "SW2_2") (pintype "bidirectional"))
      (node (ref "IC4") (pin "22") (pinfunction "GPA1_22") (pintype "bidirectional"))
    )
    (net (code "12") (name "GPA2") (class "Default")
      (node (ref "B3") (pin "2") (pinfunction "SW2_2") (pintype "bidirectional"))
      (node (ref "IC4") (pin "23") (pinfunction "GPA2_23") (pintype "bidirectional"))
    )
    (net (code "13") (name "GPA3") (class "Default")
      (node (ref "B4") (pin "2") (pinfunction "SW2_2") (pintype "bidirectional"))
      (node (ref "IC4") (pin "24") (pinfunction "GPA3_24") (pintype "bidirectional"))
    )
    (net (code "14") (name "GPA4") (class "Default")
      (node (ref "B5") (pin "2") (pinfunction "SW2_2") (pintype "bidirectional"))
      (node (ref "IC4") (pin "25") (pinfunction "GPA4_25") (pintype "bidirectional"))
    )
    (net (code "15") (name "GPA5") (class "Default")
      (node (ref "B6") (pin "2") (pinfunction "SW2_2") (pintype "bidirectional"))
      (node (ref "IC4") (pin "26") (pinfunction "GPA5_26") (pintype "bidirectional"))
    )
    (net (code "16") (name "GPA6") (class "Default")
      (node (ref "B7") (pin "2") (pinfunction "SW2_2") (pintype "bidirectional"))
      (node (ref "IC4") (pin "27") (pinfunction "GPA6_27") (pintype "bidirectional"))
    )
    (net (code "17") (name "GPA7") (class "Default")
      (node (ref "B8") (pin "2") (pinfunction "SW2_2") (pintype "bidirectional"))
      (node (ref "IC4") (pin "28") (pinfunction "GPA7_28") (pintype "bidirectional"))
    )
    (net (code "18") (name "GPB0") (class "Default")
      (node (ref "B9") (pin "2") (pinfunction "SW2_2") (pintype "bidirectional"))
      (node (ref "IC4") (pin "1") (pinfunction "GPB0_1") (pintype "bidirectional"))
    )
    (net (code "19") (name "GPB1") (class "Default")
      (node (ref "B10") (pin "2") (pinfunction "SW2_2") (pintype "bidirectional"))
      (node (ref "IC4") (pin "2") (pinfunction "GPB1_2") (pintype "bidirectional"))
    )
    (net (code "20") (name "GPB2") (class "Default")
      (node (ref "B11") (pin "2") (pinfunction "SW2_2") (pintype "bidirectional"))
      (node (ref "IC4") (pin "3") (pinfunction "GPB2_3") (pintype "bidirectional"))
    )
    (net (code "21") (name "GPB3") (class "Default")
      (node (ref "B12") (pin "2") (pinfunction "SW2_2") (pintype "bidirectional"))
      (node (ref "IC4") (pin "4") (pinfunction "GPB3_4") (pintype "bidirectional"))
    )
    (net (code "22") (name "GPB4") (class "Default")
      (node (ref "B13") (pin "2") (pinfunction "SW2_2") (pintype "bidirectional"))
      (node (ref "IC4") (pin "5") (pinfunction "GPB4_5") (pintype "bidirectional"))
    )
    (net (code "23") (name "GPB5") (class "Default")
      (node (ref "B14") (pin "2") (pinfunction "SW2_2") (pintype "bidirectional"))
      (node (ref "IC4") (pin "6") (pinfunction "GPB5_6") (pintype "bidirectional"))
    )
    (net (code "24") (name "GPB6") (class "Default")
      (node (ref "B15") (pin "2") (pinfunction "SW2_2") (pintype "bidirectional"))
      (node (ref "IC4") (pin "7") (pinfunction "GPB6_7") (pintype "bidirectional"))
    )
    (net (code "25") (name "GPB7") (class "Default")
      (node (ref "B16") (pin "2") (pinfunction "SW2_2") (pintype "bidirectional"))
      (node (ref "IC4") (pin "8") (pinfunction "GPB7_8") (pintype "bidirectional"))
    )
    (net (code "26") (name "I2C_SCL") (class "Default")
      (node (ref "IC2") (pin "12") (pinfunction "SCL_12") (pintype "input"))
      (node (ref "IC3") (pin "26") (pinfunction "SCL_26") (pintype "input"))
      (node (ref "IC4") (pin "12") (pinfunction "SCL_12") (pintype "input"))
      (node (ref "JP4") (pin "2") (pinfunction "2_2") (pintype "passive"))
      (node (ref "R2") (pin "1") (pinfunction "1_1") (pintype "passive"))
      (node (ref "SERIAL") (pin "4") (pinfunction "4_4") (pintype "passive"))
    )
    (net (code "27") (name "I2C_SDA") (class "Default")
      (node (ref "IC2") (pin "13") (pinfunction "SDA_13") (pintype "bidirectional"))
      (node (ref "IC3") (pin "27") (pinfunction "SDA_27") (pintype "input"))
      (node (ref "IC4") (pin "13") (pinfunction "SDA_13") (pintype "bidirectional"))
      (node (ref "JP4") (pin "1") (pinfunction "1_1") (pintype "passive"))
      (node (ref "R1") (pin "1") (pinfunction "1_1") (pintype "passive"))
      (node (ref "SERIAL") (pin "3") (pinfunction "3_3") (pintype "passive"))
    )
    (net (code "28") (name "L0") (class "Default")
      (node (ref "B1") (pin "L1") (pinfunction "L1_L1") (pintype "bidirectional"))
      (node (ref "B1") (pin "L2") (pinfunction "L2_L2") (pintype "bidirectional"))
      (node (ref "R37") (pin "1") (pinfunction "1_1") (pintype "passive"))
    )
    (net (code "29") (name "L1") (class "Default")
      (node (ref "B2") (pin "L1") (pinfunction "L1_L1") (pintype "bidirectional"))
      (node (ref "B2") (pin "L2") (pinfunction "L2_L2") (pintype "bidirectional"))
      (node (ref "R36") (pin "1") (pinfunction "1_1") (pintype "passive"))
    )
    (net (code "30") (name "L2") (class "Default")
      (node (ref "B3") (pin "L1") (pinfunction "L1_L1") (pintype "bidirectional"))
      (node (ref "B3") (pin "L2") (pinfunction "L2_L2") (pintype "bidirectional"))
      (node (ref "R35") (pin "1") (pinfunction "1_1") (pintype "passive"))
    )
    (net (code "31") (name "L3") (class "Default")
      (node (ref "B4") (pin "L1") (pinfunction "L1_L1") (pintype "bidirectional"))
      (node (ref "B4") (pin "L2") (pinfunction "L2_L2") (pintype "bidirectional"))
      (node (ref "R34") (pin "1") (pinfunction "1_1") (pintype "passive"))
    )
    (net (code "32") (name "L4") (class "Default")
      (node (ref "B5") (pin "L1") (pinfunction "L1_L1") (pintype "bidirectional"))
      (node (ref "B5") (pin "L2") (pinfunction "L2_L2") (pintype "bidirectional"))
      (node (ref "R33") (pin "1") (pinfunction "1_1") (pintype "passive"))
    )
    (net (code "33") (name "L5") (class "Default")
      (node (ref "B6") (pin "L1") (pinfunction "L1_L1") (pintype "bidirectional"))
      (node (ref "B6") (pin "L2") (pinfunction "L2_L2") (pintype "bidirectional"))
      (node (ref "R32") (pin "1") (pinfunction "1_1") (pintype "passive"))
    )
    (net (code "34") (name "L6") (class "Default")
      (node (ref "B7") (pin "L1") (pinfunction "L1_L1") (pintype "bidirectional"))
      (node (ref "B7") (pin "L2") (pinfunction "L2_L2") (pintype "bidirectional"))
      (node (ref "R31") (pin "1") (pinfunction "1_1") (pintype "passive"))
    )
    (net (code "35") (name "L7") (class "Default")
      (node (ref "B8") (pin "L1") (pinfunction "L1_L1") (pintype "bidirectional"))
      (node (ref "B8") (pin "L2") (pinfunction "L2_L2") (pintype "bidirectional"))
      (node (ref "R30") (pin "1") (pinfunction "1_1") (pintype "passive"))
    )
    (net (code "36") (name "L8") (class "Default")
      (node (ref "B9") (pin "L1") (pinfunction "L1_L1") (pintype "bidirectional"))
      (node (ref "B9") (pin "L2") (pinfunction "L2_L2") (pintype "bidirectional"))
      (node (ref "R29") (pin "1") (pinfunction "1_1") (pintype "passive"))
    )
    (net (code "37") (name "L9") (class "Default")
      (node (ref "B10") (pin "L1") (pinfunction "L1_L1") (pintype "bidirectional"))
      (node (ref "B10") (pin "L2") (pinfunction "L2_L2") (pintype "bidirectional"))
      (node (ref "R28") (pin "1") (pinfunction "1_1") (pintype "passive"))
    )
    (net (code "38") (name "L10") (class "Default")
      (node (ref "B11") (pin "L1") (pinfunction "L1_L1") (pintype "bidirectional"))
      (node (ref "B11") (pin "L2") (pinfunction "L2_L2") (pintype "bidirectional"))
      (node (ref "R27") (pin "1") (pinfunction "1_1") (pintype "passive"))
    )
    (net (code "39") (name "L11") (class "Default")
      (node (ref "B12") (pin "L1") (pinfunction "L1_L1") (pintype "bidirectional"))
      (node (ref "B12") (pin "L2") (pinfunction "L2_L2") (pintype "bidirectional"))
      (node (ref "R26") (pin "1") (pinfunction "1_1") (pintype "passive"))
    )
    (net (code "40") (name "L12") (class "Default")
      (node (ref "B13") (pin "L1") (pinfunction "L1_L1") (pintype "bidirectional"))
      (node (ref "B13") (pin "L2") (pinfunction "L2_L2") (pintype "bidirectional"))
      (node (ref "R25") (pin "1") (pinfunction "1_1") (pintype "passive"))
    )
    (net (code "41") (name "L13") (class "Default")
      (node (ref "B14") (pin "L1") (pinfunction "L1_L1") (pintype "bidirectional"))
      (node (ref "B14") (pin "L2") (pinfunction "L2_L2") (pintype "bidirectional"))
      (node (ref "R24") (pin "1") (pinfunction "1_1") (pintype "passive"))
    )
    (net (code "42") (name "L14") (class "Default")
      (node (ref "B15") (pin "L1") (pinfunction "L1_L1") (pintype "bidirectional"))
      (node (ref "B15") (pin "L2") (pinfunction "L2_L2") (pintype "bidirectional"))
      (node (ref "R23") (pin "1") (pinfunction "1_1") (pintype "passive"))
    )
    (net (code "43") (name "L15") (class "Default")
      (node (ref "B16") (pin "L1") (pinfunction "L1_L1") (pintype "bidirectional"))
      (node (ref "B16") (pin "L2") (pinfunction "L2_L2") (pintype "bidirectional"))
      (node (ref "R22") (pin "1") (pinfunction "1_1") (pintype "passive"))
    )
    (net (code "44") (name "Net-(D1-A)") (class "Default")
      (node (ref "D1") (pin "2") (pinfunction "A_2") (pintype "passive"))
      (node (ref "OK4") (pin "2") (pinfunction "C_2") (pintype "passive"))
      (node (ref "X1") (pin "4") (pinfunction "F_4") (pintype "passive"))
    )
    (net (code "45") (name "Net-(D1-C)") (class "Default")
      (node (ref "D1") (pin "1") (pinfunction "C_1") (pintype "passive"))
      (node (ref "OK4") (pin "1") (pinfunction "A_1") (pintype "passive"))
      (node (ref "R19") (pin "2") (pinfunction "2_2") (pintype "passive"))
    )
    (net (code "46") (name "Net-(D2-A)") (class "Default")
      (node (ref "D2") (pin "2") (pinfunction "A_2") (pintype "passive"))
      (node (ref "OK4") (pin "4") (pinfunction "C_4") (pintype "passive"))
      (node (ref "X1") (pin "3") (pinfunction "F_3") (pintype "passive"))
    )
    (net (code "47") (name "Net-(D2-C)") (class "Default")
      (node (ref "D2") (pin "1") (pinfunction "C_1") (pintype "passive"))
      (node (ref "OK4") (pin "3") (pinfunction "A_3") (pintype "passive"))
      (node (ref "R20") (pin "2") (pinfunction "2_2") (pintype "passive"))
    )
    (net (code "48") (name "Net-(D3-A)") (class "Default")
      (node (ref "D3") (pin "2") (pinfunction "A_2") (pintype "passive"))
      (node (ref "OK3") (pin "4") (pinfunction "C_4") (pintype "passive"))
      (node (ref "X1") (pin "5") (pinfunction "F_5") (pintype "passive"))
    )
    (net (code "49") (name "Net-(D3-C)") (class "Default")
      (node (ref "D3") (pin "1") (pinfunction "C_1") (pintype "passive"))
      (node (ref "OK3") (pin "3") (pinfunction "A_3") (pintype "passive"))
      (node (ref "R18") (pin "2") (pinfunction "2_2") (pintype "passive"))
    )
    (net (code "50") (name "Net-(D4-A)") (class "Default")
      (node (ref "D4") (pin "2") (pinfunction "A_2") (pintype "passive"))
      (node (ref "OK3") (pin "2") (pinfunction "C_2") (pintype "passive"))
      (node (ref "X1") (pin "6") (pinfunction "F_6") (pintype "passive"))
    )
    (net (code "51") (name "Net-(D4-C)") (class "Default")
      (node (ref "D4") (pin "1") (pinfunction "C_1") (pintype "passive"))
      (node (ref "OK3") (pin "1") (pinfunction "A_1") (pintype "passive"))
      (node (ref "R17") (pin "2") (pinfunction "2_2") (pintype "passive"))
    )
    (net (code "52") (name "Net-(D5-A)") (class "Default")
      (node (ref "D5") (pin "2") (pinfunction "A_2") (pintype "passive"))
      (node (ref "OK2") (pin "4") (pinfunction "C_4") (pintype "passive"))
      (node (ref "X1") (pin "7") (pinfunction "F_7") (pintype "passive"))
    )
    (net (code "53") (name "Net-(D5-C)") (class "Default")
      (node (ref "D5") (pin "1") (pinfunction "C_1") (pintype "passive"))
      (node (ref "OK2") (pin "3") (pinfunction "A_3") (pintype "passive"))
      (node (ref "R16") (pin "2") (pinfunction "2_2") (pintype "passive"))
    )
    (net (code "54") (name "Net-(D6-A)") (class "Default")
      (node (ref "D6") (pin "2") (pinfunction "A_2") (pintype "passive"))
      (node (ref "OK2") (pin "2") (pinfunction "C_2") (pintype "passive"))
      (node (ref "X1") (pin "8") (pinfunction "F_8") (pintype "passive"))
    )
    (net (code "55") (name "Net-(D6-C)") (class "Default")
      (node (ref "D6") (pin "1") (pinfunction "C_1") (pintype "passive"))
      (node (ref "OK2") (pin "1") (pinfunction "A_1") (pintype "passive"))
      (node (ref "R15") (pin "2") (pinfunction "2_2") (pintype "passive"))
    )
    (net (code "56") (name "Net-(D7-A)") (class "Default")
      (node (ref "D7") (pin "2") (pinfunction "A_2") (pintype "passive"))
      (node (ref "OK1") (pin "4") (pinfunction "C_4") (pintype "passive"))
      (node (ref "X1") (pin "9") (pinfunction "F_9") (pintype "passive"))
    )
    (net (code "57") (name "Net-(D7-C)") (class "Default")
      (node (ref "D7") (pin "1") (pinfunction "C_1") (pintype "passive"))
      (node (ref "OK1") (pin "3") (pinfunction "A_3") (pintype "passive"))
      (node (ref "R13") (pin "2") (pinfunction "2_2") (pintype "passive"))
    )
    (net (code "58") (name "Net-(D8-A)") (class "Default")
      (node (ref "D8") (pin "2") (pinfunction "A_2") (pintype "passive"))
      (node (ref "OK1") (pin "2") (pinfunction "C_2") (pintype "passive"))
      (node (ref "X1") (pin "10") (pinfunction "F_10") (pintype "passive"))
    )
    (net (code "59") (name "Net-(D8-C)") (class "Default")
      (node (ref "D8") (pin "1") (pinfunction "C_1") (pintype "passive"))
      (node (ref "OK1") (pin "1") (pinfunction "A_1") (pintype "passive"))
      (node (ref "R14") (pin "2") (pinfunction "2_2") (pintype "passive"))
    )
    (net (code "60") (name "Net-(IC1-I1)") (class "Default")
      (node (ref "IC1") (pin "1") (pinfunction "I1_1") (pintype "input"))
      (node (ref "IC2") (pin "1") (pinfunction "GPB0_1") (pintype "bidirectional"))
    )
    (net (code "61") (name "Net-(IC1-I2)") (class "Default")
      (node (ref "IC1") (pin "2") (pinfunction "I2_2") (pintype "input"))
      (node (ref "IC2") (pin "2") (pinfunction "GPB1_2") (pintype "bidirectional"))
    )
    (net (code "62") (name "Net-(IC1-I3)") (class "Default")
      (node (ref "IC1") (pin "3") (pinfunction "I3_3") (pintype "input"))
      (node (ref "IC2") (pin "3") (pinfunction "GPB2_3") (pintype "bidirectional"))
    )
    (net (code "63") (name "Net-(IC1-I4)") (class "Default")
      (node (ref "IC1") (pin "4") (pinfunction "I4_4") (pintype "input"))
      (node (ref "IC2") (pin "4") (pinfunction "GPB3_4") (pintype "bidirectional"))
    )
    (net (code "64") (name "Net-(IC1-I5)") (class "Default")
      (node (ref "IC1") (pin "5") (pinfunction "I5_5") (pintype "input"))
      (node (ref "IC2") (pin "5") (pinfunction "GPB4_5") (pintype "bidirectional"))
    )
    (net (code "65") (name "Net-(IC1-I6)") (class "Default")
      (node (ref "IC1") (pin "6") (pinfunction "I6_6") (pintype "input"))
      (node (ref "IC2") (pin "6") (pinfunction "GPB5_6") (pintype "bidirectional"))
    )
    (net (code "66") (name "Net-(IC1-I7)") (class "Default")
      (node (ref "IC1") (pin "7") (pinfunction "I7_7") (pintype "input"))
      (node (ref "IC2") (pin "7") (pinfunction "GPB6_7") (pintype "bidirectional"))
    )
    (net (code "67") (name "Net-(IC1-I8)") (class "Default")
      (node (ref "IC1") (pin "8") (pinfunction "I8_8") (pintype "input"))
      (node (ref "IC2") (pin "8") (pinfunction "GPB7_8") (pintype "bidirectional"))
    )
    (net (code "68") (name "Net-(IC1-O1)") (class "Default")
      (node (ref "IC1") (pin "18") (pinfunction "O1_18") (pintype "open_collector"))
      (node (ref "K1") (pin "16") (pinfunction "2_16") (pintype "passive"))
    )
    (net (code "69") (name "Net-(IC1-O2)") (class "Default")
      (node (ref "IC1") (pin "17") (pinfunction "O2_17") (pintype "open_collector"))
      (node (ref "K2") (pin "16") (pinfunction "2_16") (pintype "passive"))
    )
    (net (code "70") (name "Net-(IC1-O3)") (class "Default")
      (node (ref "IC1") (pin "16") (pinfunction "O3_16") (pintype "open_collector"))
      (node (ref "K3") (pin "16") (pinfunction "2_16") (pintype "passive"))
    )
    (net (code "71") (name "Net-(IC1-O4)") (class "Default")
      (node (ref "IC1") (pin "15") (pinfunction "O4_15") (pintype "open_collector"))
      (node (ref "K4") (pin "16") (pinfunction "2_16") (pintype "passive"))
    )
    (net (code "72") (name "Net-(IC1-O5)") (class "Default")
      (node (ref "IC1") (pin "14") (pinfunction "O5_14") (pintype "open_collector"))
      (node (ref "K5") (pin "16") (pinfunction "2_16") (pintype "passive"))
    )
    (net (code "73") (name "Net-(IC1-O6)") (class "Default")
      (node (ref "IC1") (pin "13") (pinfunction "O6_13") (pintype "open_collector"))
      (node (ref "K6") (pin "16") (pinfunction "2_16") (pintype "passive"))
    )
    (net (code "74") (name "Net-(IC1-O7)") (class "Default")
      (node (ref "IC1") (pin "12") (pinfunction "O7_12") (pintype "open_collector"))
      (node (ref "K7") (pin "16") (pinfunction "2_16") (pintype "passive"))
    )
    (net (code "75") (name "Net-(IC1-O8)") (class "Default")
      (node (ref "IC1") (pin "11") (pinfunction "O8_11") (pintype "open_collector"))
      (node (ref "K8") (pin "16") (pinfunction "2_16") (pintype "passive"))
    )
    (net (code "76") (name "Net-(IC2-GPA0)") (class "Default")
      (node (ref "IC2") (pin "21") (pinfunction "GPA0_21") (pintype "bidirectional"))
      (node (ref "OK1") (pin "8") (pinfunction "COL_8") (pintype "passive"))
    )
    (net (code "77") (name "Net-(IC2-GPA1)") (class "Default")
      (node (ref "IC2") (pin "22") (pinfunction "GPA1_22") (pintype "bidirectional"))
      (node (ref "OK1") (pin "6") (pinfunction "COL_6") (pintype "passive"))
    )
    (net (code "78") (name "Net-(IC2-GPA2)") (class "Default")
      (node (ref "IC2") (pin "23") (pinfunction "GPA2_23") (pintype "bidirectional"))
      (node (ref "OK2") (pin "8") (pinfunction "COL_8") (pintype "passive"))
    )
    (net (code "79") (name "Net-(IC2-GPA3)") (class "Default")
      (node (ref "IC2") (pin "24") (pinfunction "GPA3_24") (pintype "bidirectional"))
      (node (ref "OK2") (pin "6") (pinfunction "COL_6") (pintype "passive"))
    )
    (net (code "80") (name "Net-(IC2-GPA4)") (class "Default")
      (node (ref "IC2") (pin "25") (pinfunction "GPA4_25") (pintype "bidirectional"))
      (node (ref "OK3") (pin "8") (pinfunction "COL_8") (pintype "passive"))
    )
    (net (code "81") (name "Net-(IC2-GPA5)") (class "Default")
      (node (ref "IC2") (pin "26") (pinfunction "GPA5_26") (pintype "bidirectional"))
      (node (ref "OK3") (pin "6") (pinfunction "COL_6") (pintype "passive"))
    )
    (net (code "82") (name "Net-(IC2-GPA6)") (class "Default")
      (node (ref "IC2") (pin "27") (pinfunction "GPA6_27") (pintype "bidirectional"))
      (node (ref "OK4") (pin "8") (pinfunction "COL_8") (pintype "passive"))
    )
    (net (code "83") (name "Net-(IC2-GPA7)") (class "Default")
      (node (ref "IC2") (pin "28") (pinfunction "GPA7_28") (pintype "bidirectional"))
      (node (ref "OK4") (pin "6") (pinfunction "COL_6") (pintype "passive"))
    )
    (net (code "84") (name "Net-(IC3-L0)") (class "Default")
      (node (ref "IC3") (pin "6") (pinfunction "L0_6") (pintype "output"))
      (node (ref "R37") (pin "2") (pinfunction "2_2") (pintype "passive"))
    )
    (net (code "85") (name "Net-(IC3-L1)") (class "Default")
      (node (ref "IC3") (pin "7") (pinfunction "L1_7") (pintype "output"))
      (node (ref "R36") (pin "2") (pinfunction "2_2") (pintype "passive"))
    )
    (net (code "86") (name "Net-(IC3-L2)") (class "Default")
      (node (ref "IC3") (pin "8") (pinfunction "L2_8") (pintype "output"))
      (node (ref "R35") (pin "2") (pinfunction "2_2") (pintype "passive"))
    )
    (net (code "87") (name "Net-(IC3-L3)") (class "Default")
      (node (ref "IC3") (pin "9") (pinfunction "L3_9") (pintype "output"))
      (node (ref "R34") (pin "2") (pinfunction "2_2") (pintype "passive"))
    )
    (net (code "88") (name "Net-(IC3-L4)") (class "Default")
      (node (ref "IC3") (pin "10") (pinfunction "L4_10") (pintype "output"))
      (node (ref "R33") (pin "2") (pinfunction "2_2") (pintype "passive"))
    )
    (net (code "89") (name "Net-(IC3-L5)") (class "Default")
      (node (ref "IC3") (pin "11") (pinfunction "L5_11") (pintype "output"))
      (node (ref "R32") (pin "2") (pinfunction "2_2") (pintype "passive"))
    )
    (net (code "90") (name "Net-(IC3-L6)") (class "Default")
      (node (ref "IC3") (pin "12") (pinfunction "L6_12") (pintype "output"))
      (node (ref "R31") (pin "2") (pinfunction "2_2") (pintype "passive"))
    )
    (net (code "91") (name "Net-(IC3-L7)") (class "Default")
      (node (ref "IC3") (pin "13") (pinfunction "L7_13") (pintype "output"))
      (node (ref "R30") (pin "2") (pinfunction "2_2") (pintype "passive"))
    )
    (net (code "92") (name "Net-(IC3-L8)") (class "Default")
      (node (ref "IC3") (pin "15") (pinfunction "L8_15") (pintype "output"))
      (node (ref "R29") (pin "2") (pinfunction "2_2") (pintype "passive"))
    )
    (net (code "93") (name "Net-(IC3-L9)") (class "Default")
      (node (ref "IC3") (pin "16") (pinfunction "L9_16") (pintype "output"))
      (node (ref "R28") (pin "2") (pinfunction "2_2") (pintype "passive"))
    )
    (net (code "94") (name "Net-(IC3-L10)") (class "Default")
      (node (ref "IC3") (pin "17") (pinfunction "L10_17") (pintype "output"))
      (node (ref "R27") (pin "2") (pinfunction "2_2") (pintype "passive"))
    )
    (net (code "95") (name "Net-(IC3-L11)") (class "Default")
      (node (ref "IC3") (pin "18") (pinfunction "L11_18") (pintype "output"))
      (node (ref "R26") (pin "2") (pinfunction "2_2") (pintype "passive"))
    )
    (net (code "96") (name "Net-(IC3-L12)") (class "Default")
      (node (ref "IC3") (pin "19") (pinfunction "L12_19") (pintype "output"))
      (node (ref "R25") (pin "2") (pinfunction "2_2") (pintype "passive"))
    )
    (net (code "97") (name "Net-(IC3-L13)") (class "Default")
      (node (ref "IC3") (pin "20") (pinfunction "L13_20") (pintype "output"))
      (node (ref "R24") (pin "2") (pinfunction "2_2") (pintype "passive"))
    )
    (net (code "98") (name "Net-(IC3-L14)") (class "Default")
      (node (ref "IC3") (pin "21") (pinfunction "L14_21") (pintype "output"))
      (node (ref "R23") (pin "2") (pinfunction "2_2") (pintype "passive"))
    )
    (net (code "99") (name "Net-(IC3-L15)") (class "Default")
      (node (ref "IC3") (pin "22") (pinfunction "L15_22") (pintype "output"))
      (node (ref "R22") (pin "2") (pinfunction "2_2") (pintype "passive"))
    )
    (net (code "100") (name "Net-(JP3-Pad2)") (class "Default")
      (node (ref "JP3") (pin "2") (pinfunction "2_2") (pintype "passive"))
      (node (ref "JP5") (pin "2") (pinfunction "2_2") (pintype "passive"))
    )
    (net (code "101") (name "Net-(JP3-Pad4)") (class "Default")
      (node (ref "JP3") (pin "4") (pinfunction "4_4") (pintype "passive"))
      (node (ref "JP5") (pin "4") (pinfunction "4_4") (pintype "passive"))
    )
    (net (code "102") (name "Net-(JP3-Pad5)") (class "Default")
      (node (ref "JP3") (pin "5") (pinfunction "5_5") (pintype "passive"))
      (node (ref "JP5") (pin "5") (pinfunction "5_5") (pintype "passive"))
    )
    (net (code "103") (name "Net-(JP3-Pad6)") (class "Default")
      (node (ref "JP3") (pin "6") (pinfunction "6_6") (pintype "passive"))
      (node (ref "JP5") (pin "6") (pinfunction "6_6") (pintype "passive"))
    )
    (net (code "104") (name "Net-(K1B-S)") (class "Default")
      (node (ref "K1") (pin "S1") (pinfunction "S_S1") (pintype "passive"))
      (node (ref "X1") (pin "23") (pinfunction "F_23") (pintype "passive"))
    )
    (net (code "105") (name "Net-(K2B-S)") (class "Default")
      (node (ref "K2") (pin "S1") (pinfunction "S_S1") (pintype "passive"))
      (node (ref "X1") (pin "22") (pinfunction "F_22") (pintype "passive"))
    )
    (net (code "106") (name "Net-(K3B-S)") (class "Default")
      (node (ref "K3") (pin "S1") (pinfunction "S_S1") (pintype "passive"))
      (node (ref "X1") (pin "21") (pinfunction "F_21") (pintype "passive"))
    )
    (net (code "107") (name "Net-(K4B-S)") (class "Default")
      (node (ref "K4") (pin "S1") (pinfunction "S_S1") (pintype "passive"))
      (node (ref "X1") (pin "20") (pinfunction "F_20") (pintype "passive"))
    )
    (net (code "108") (name "Net-(K5B-S)") (class "Default")
      (node (ref "K5") (pin "S1") (pinfunction "S_S1") (pintype "passive"))
      (node (ref "X1") (pin "19") (pinfunction "F_19") (pintype "passive"))
    )
    (net (code "109") (name "Net-(K6B-S)") (class "Default")
      (node (ref "K6") (pin "S1") (pinfunction "S_S1") (pintype "passive"))
      (node (ref "X1") (pin "18") (pinfunction "F_18") (pintype "passive"))
    )
    (net (code "110") (name "Net-(K7B-S)") (class "Default")
      (node (ref "K7") (pin "S1") (pinfunction "S_S1") (pintype "passive"))
      (node (ref "X1") (pin "17") (pinfunction "F_17") (pintype "passive"))
    )
    (net (code "111") (name "Net-(K8B-S)") (class "Default")
      (node (ref "K8") (pin "S1") (pinfunction "S_S1") (pintype "passive"))
      (node (ref "X1") (pin "16") (pinfunction "F_16") (pintype "passive"))
    )
    (net (code "112") (name "Net-(U$7-P$2)") (class "Default")
      (node (ref "R4") (pin "1") (pinfunction "1_1") (pintype "passive"))
      (node (ref "U$7") (pin "A2") (pinfunction "P$2_A2") (pintype "bidirectional"))
    )
    (net (code "113") (name "Net-(U$7-P$3)") (class "Default")
      (node (ref "R3") (pin "1") (pinfunction "1_1") (pintype "passive"))
      (node (ref "U$7") (pin "A3") (pinfunction "P$3_A3") (pintype "bidirectional"))
    )
    (net (code "114") (name "RES") (class "Default")
      (node (ref "GND") (pin "RES") (pinfunction "RES_RES") (pintype "bidirectional"))
      (node (ref "RESET") (pin "1") (pinfunction "1_1") (pintype "passive"))
      (node (ref "RESETA") (pin "1") (pinfunction "1_1") (pintype "passive"))
    )
    (net (code "115") (name "SDI_MOSI") (class "Default")
      (node (ref "JP2") (pin "2") (pinfunction "2_2") (pintype "passive"))
      (node (ref "SERIAL") (pin "8") (pinfunction "8_8") (pintype "passive"))
    )
    (net (code "116") (name "SDI_SCLK") (class "Default")
      (node (ref "JP2") (pin "1") (pinfunction "1_1") (pintype "passive"))
      (node (ref "SERIAL") (pin "7") (pinfunction "7_7") (pintype "passive"))
    )
    (net (code "117") (name "SLIDER_IN") (class "Default")
      (node (ref "C7") (pin "1") (pinfunction "1_1") (pintype "passive"))
      (node (ref "GND") (pin "A0") (pinfunction "A0_A0") (pintype "bidirectional"))
      (node (ref "POT1") (pin "2A") (pinfunction "S_2A") (pintype "passive"))
      (node (ref "SERIAL") (pin "5") (pinfunction "5_5") (pintype "passive"))
    )
    (net (code "118") (name "VIN") (class "Default")
      (node (ref "GND") (pin "VIN") (pinfunction "VIN_VIN") (pintype "bidirectional"))
    )
    (net (code "119") (name "unconnected-(B1-PadL3)") (class "Default")
      (node (ref "B1") (pin "L3") (pinfunction "L3_L3") (pintype "bidirectional"))
    )
    (net (code "120") (name "unconnected-(B1-PadL4)") (class "Default")
      (node (ref "B1") (pin "L4") (pinfunction "L4_L4") (pintype "bidirectional"))
    )
    (net (code "121") (name "unconnected-(B1-PadLC2)") (class "Default")
      (node (ref "B1") (pin "LC2") (pinfunction "LC2_LC2") (pintype "bidirectional"))
    )
    (net (code "122") (name "unconnected-(B2-PadL3)") (class "Default")
      (node (ref "B2") (pin "L3") (pinfunction "L3_L3") (pintype "bidirectional"))
    )
    (net (code "123") (name "unconnected-(B2-PadL4)") (class "Default")
      (node (ref "B2") (pin "L4") (pinfunction "L4_L4") (pintype "bidirectional"))
    )
    (net (code "124") (name "unconnected-(B2-PadLC2)") (class "Default")
      (node (ref "B2") (pin "LC2") (pinfunction "LC2_LC2") (pintype "bidirectional"))
    )
    (net (code "125") (name "unconnected-(B3-PadL3)") (class "Default")
      (node (ref "B3") (pin "L3") (pinfunction "L3_L3") (pintype "bidirectional"))
    )
    (net (code "126") (name "unconnected-(B3-PadL4)") (class "Default")
      (node (ref "B3") (pin "L4") (pinfunction "L4_L4") (pintype "bidirectional"))
    )
    (net (code "127") (name "unconnected-(B3-PadLC2)") (class "Default")
      (node (ref "B3") (pin "LC2") (pinfunction "LC2_LC2") (pintype "bidirectional"))
    )
    (net (code "128") (name "unconnected-(B4-PadL3)") (class "Default")
      (node (ref "B4") (pin "L3") (pinfunction "L3_L3") (pintype "bidirectional"))
    )
    (net (code "129") (name "unconnected-(B4-PadL4)") (class "Default")
      (node (ref "B4") (pin "L4") (pinfunction "L4_L4") (pintype "bidirectional"))
    )
    (net (code "130") (name "unconnected-(B4-PadLC2)") (class "Default")
      (node (ref "B4") (pin "LC2") (pinfunction "LC2_LC2") (pintype "bidirectional"))
    )
    (net (code "131") (name "unconnected-(B5-PadL3)") (class "Default")
      (node (ref "B5") (pin "L3") (pinfunction "L3_L3") (pintype "bidirectional"))
    )
    (net (code "132") (name "unconnected-(B5-PadL4)") (class "Default")
      (node (ref "B5") (pin "L4") (pinfunction "L4_L4") (pintype "bidirectional"))
    )
    (net (code "133") (name "unconnected-(B5-PadLC2)") (class "Default")
      (node (ref "B5") (pin "LC2") (pinfunction "LC2_LC2") (pintype "bidirectional"))
    )
    (net (code "134") (name "unconnected-(B6-PadL3)") (class "Default")
      (node (ref "B6") (pin "L3") (pinfunction "L3_L3") (pintype "bidirectional"))
    )
    (net (code "135") (name "unconnected-(B6-PadL4)") (class "Default")
      (node (ref "B6") (pin "L4") (pinfunction "L4_L4") (pintype "bidirectional"))
    )
    (net (code "136") (name "unconnected-(B6-PadLC2)") (class "Default")
      (node (ref "B6") (pin "LC2") (pinfunction "LC2_LC2") (pintype "bidirectional"))
    )
    (net (code "137") (name "unconnected-(B7-PadL3)") (class "Default")
      (node (ref "B7") (pin "L3") (pinfunction "L3_L3") (pintype "bidirectional"))
    )
    (net (code "138") (name "unconnected-(B7-PadL4)") (class "Default")
      (node (ref "B7") (pin "L4") (pinfunction "L4_L4") (pintype "bidirectional"))
    )
    (net (code "139") (name "unconnected-(B7-PadLC2)") (class "Default")
      (node (ref "B7") (pin "LC2") (pinfunction "LC2_LC2") (pintype "bidirectional"))
    )
    (net (code "140") (name "unconnected-(B8-PadL3)") (class "Default")
      (node (ref "B8") (pin "L3") (pinfunction "L3_L3") (pintype "bidirectional"))
    )
    (net (code "141") (name "unconnected-(B8-PadL4)") (class "Default")
      (node (ref "B8") (pin "L4") (pinfunction "L4_L4") (pintype "bidirectional"))
    )
    (net (code "142") (name "unconnected-(B8-PadLC2)") (class "Default")
      (node (ref "B8") (pin "LC2") (pinfunction "LC2_LC2") (pintype "bidirectional"))
    )
    (net (code "143") (name "unconnected-(B9-PadL3)") (class "Default")
      (node (ref "B9") (pin "L3") (pinfunction "L3_L3") (pintype "bidirectional"))
    )
    (net (code "144") (name "unconnected-(B9-PadL4)") (class "Default")
      (node (ref "B9") (pin "L4") (pinfunction "L4_L4") (pintype "bidirectional"))
    )
    (net (code "145") (name "unconnected-(B9-PadLC2)") (class "Default")
      (node (ref "B9") (pin "LC2") (pinfunction "LC2_LC2") (pintype "bidirectional"))
    )
    (net (code "146") (name "unconnected-(B10-PadL3)") (class "Default")
      (node (ref "B10") (pin "L3") (pinfunction "L3_L3") (pintype "bidirectional"))
    )
    (net (code "147") (name "unconnected-(B10-PadL4)") (class "Default")
      (node (ref "B10") (pin "L4") (pinfunction "L4_L4") (pintype "bidirectional"))
    )
    (net (code "148") (name "unconnected-(B10-PadLC2)") (class "Default")
      (node (ref "B10") (pin "LC2") (pinfunction "LC2_LC2") (pintype "bidirectional"))
    )
    (net (code "149") (name "unconnected-(B11-PadL3)") (class "Default")
      (node (ref "B11") (pin "L3") (pinfunction "L3_L3") (pintype "bidirectional"))
    )
    (net (code "150") (name "unconnected-(B11-PadL4)") (class "Default")
      (node (ref "B11") (pin "L4") (pinfunction "L4_L4") (pintype "bidirectional"))
    )
    (net (code "151") (name "unconnected-(B11-PadLC2)") (class "Default")
      (node (ref "B11") (pin "LC2") (pinfunction "LC2_LC2") (pintype "bidirectional"))
    )
    (net (code "152") (name "unconnected-(B12-PadL3)") (class "Default")
      (node (ref "B12") (pin "L3") (pinfunction "L3_L3") (pintype "bidirectional"))
    )
    (net (code "153") (name "unconnected-(B12-PadL4)") (class "Default")
      (node (ref "B12") (pin "L4") (pinfunction "L4_L4") (pintype "bidirectional"))
    )
    (net (code "154") (name "unconnected-(B12-PadLC2)") (class "Default")
      (node (ref "B12") (pin "LC2") (pinfunction "LC2_LC2") (pintype "bidirectional"))
    )
    (net (code "155") (name "unconnected-(B13-PadL3)") (class "Default")
      (node (ref "B13") (pin "L3") (pinfunction "L3_L3") (pintype "bidirectional"))
    )
    (net (code "156") (name "unconnected-(B13-PadL4)") (class "Default")
      (node (ref "B13") (pin "L4") (pinfunction "L4_L4") (pintype "bidirectional"))
    )
    (net (code "157") (name "unconnected-(B13-PadLC2)") (class "Default")
      (node (ref "B13") (pin "LC2") (pinfunction "LC2_LC2") (pintype "bidirectional"))
    )
    (net (code "158") (name "unconnected-(B14-PadL3)") (class "Default")
      (node (ref "B14") (pin "L3") (pinfunction "L3_L3") (pintype "bidirectional"))
    )
    (net (code "159") (name "unconnected-(B14-PadL4)") (class "Default")
      (node (ref "B14") (pin "L4") (pinfunction "L4_L4") (pintype "bidirectional"))
    )
    (net (code "160") (name "unconnected-(B14-PadLC2)") (class "Default")
      (node (ref "B14") (pin "LC2") (pinfunction "LC2_LC2") (pintype "bidirectional"))
    )
    (net (code "161") (name "unconnected-(B15-PadL3)") (class "Default")
      (node (ref "B15") (pin "L3") (pinfunction "L3_L3") (pintype "bidirectional"))
    )
    (net (code "162") (name "unconnected-(B15-PadL4)") (class "Default")
      (node (ref "B15") (pin "L4") (pinfunction "L4_L4") (pintype "bidirectional"))
    )
    (net (code "163") (name "unconnected-(B15-PadLC2)") (class "Default")
      (node (ref "B15") (pin "LC2") (pinfunction "LC2_LC2") (pintype "bidirectional"))
    )
    (net (code "164") (name "unconnected-(B16-PadL3)") (class "Default")
      (node (ref "B16") (pin "L3") (pinfunction "L3_L3") (pintype "bidirectional"))
    )
    (net (code "165") (name "unconnected-(B16-PadL4)") (class "Default")
      (node (ref "B16") (pin "L4") (pinfunction "L4_L4") (pintype "bidirectional"))
    )
    (net (code "166") (name "unconnected-(B16-PadLC2)") (class "Default")
      (node (ref "B16") (pin "LC2") (pinfunction "LC2_LC2") (pintype "bidirectional"))
    )
    (net (code "167") (name "unconnected-(GND-*D5-PadD5)") (class "Default")
      (node (ref "GND") (pin "D5") (pinfunction "*D5_D5") (pintype "bidirectional"))
    )
    (net (code "168") (name "unconnected-(GND-*D6-PadD6)") (class "Default")
      (node (ref "GND") (pin "D6") (pinfunction "*D6_D6") (pintype "bidirectional"))
    )
    (net (code "169") (name "unconnected-(GND-*D9-PadD9)") (class "Default")
      (node (ref "GND") (pin "D9") (pinfunction "*D9_D9") (pintype "bidirectional"))
    )
    (net (code "170") (name "unconnected-(GND-*D10-PadD10)") (class "Default")
      (node (ref "GND") (pin "D10") (pinfunction "*D10_D10") (pintype "bidirectional"))
    )
    (net (code "171") (name "unconnected-(GND-*D11-PadD11)") (class "Default")
      (node (ref "GND") (pin "D11") (pinfunction "*D11_D11") (pintype "bidirectional"))
    )
    (net (code "172") (name "unconnected-(GND-Pad3.3V)") (class "Default")
      (node (ref "GND") (pin "3.3V") (pinfunction "3.3V_3.3V") (pintype "bidirectional"))
    )
    (net (code "173") (name "unconnected-(GND-PadA2)") (class "Default")
      (node (ref "GND") (pin "A2") (pinfunction "A2_A2") (pintype "bidirectional"))
    )
    (net (code "174") (name "unconnected-(GND-PadA3)") (class "Default")
      (node (ref "GND") (pin "A3") (pinfunction "A3_A3") (pintype "bidirectional"))
    )
    (net (code "175") (name "unconnected-(GND-PadA4)") (class "Default")
      (node (ref "GND") (pin "A4") (pinfunction "A4_A4") (pintype "bidirectional"))
    )
    (net (code "176") (name "unconnected-(GND-PadA5)") (class "Default")
      (node (ref "GND") (pin "A5") (pinfunction "A5_A5") (pintype "bidirectional"))
    )
    (net (code "177") (name "unconnected-(GND-PadAREF)") (class "Default")
      (node (ref "GND") (pin "AREF") (pinfunction "AREF_AREF") (pintype "bidirectional"))
    )
    (net (code "178") (name "unconnected-(GND-PadD4)") (class "Default")
      (node (ref "GND") (pin "D4") (pinfunction "D4_D4") (pintype "bidirectional"))
    )
    (net (code "179") (name "unconnected-(GND-PadD8)") (class "Default")
      (node (ref "GND") (pin "D8") (pinfunction "D8_D8") (pintype "bidirectional"))
    )
    (net (code "180") (name "unconnected-(GND-PadD12)") (class "Default")
      (node (ref "GND") (pin "D12") (pinfunction "D12_D12") (pintype "bidirectional"))
    )
    (net (code "181") (name "unconnected-(GND-PadD13)") (class "Default")
      (node (ref "GND") (pin "D13") (pinfunction "D13_D13") (pintype "bidirectional"))
    )
    (net (code "182") (name "unconnected-(GND-PadRX)") (class "Default")
      (node (ref "GND") (pin "RX") (pinfunction "RX_RX") (pintype "bidirectional"))
    )
    (net (code "183") (name "unconnected-(GND-PadTX)") (class "Default")
      (node (ref "GND") (pin "TX") (pinfunction "TX_TX") (pintype "bidirectional"))
    )
    (net (code "184") (name "unconnected-(IC2-INTA-Pad20)") (class "Default")
      (node (ref "IC2") (pin "20") (pinfunction "INTA_20") (pintype "output"))
    )
    (net (code "185") (name "unconnected-(IC2-INTB-Pad19)") (class "Default")
      (node (ref "IC2") (pin "19") (pinfunction "INTB_19") (pintype "output"))
    )
    (net (code "186") (name "unconnected-(IC4-INTA-Pad20)") (class "Default")
      (node (ref "IC4") (pin "20") (pinfunction "INTA_20") (pintype "output"))
    )
    (net (code "187") (name "unconnected-(IC4-INTB-Pad19)") (class "Default")
      (node (ref "IC4") (pin "19") (pinfunction "INTB_19") (pintype "output"))
    )
    (net (code "188") (name "unconnected-(JP1-Pad1)") (class "Default")
      (node (ref "JP1") (pin "1") (pinfunction "1_1") (pintype "passive"))
    )
    (net (code "189") (name "unconnected-(JP1-Pad2)") (class "Default")
      (node (ref "JP1") (pin "2") (pinfunction "2_2") (pintype "passive"))
    )
    (net (code "190") (name "unconnected-(K1B-O-PadO1)") (class "Default")
      (node (ref "K1") (pin "O1") (pinfunction "O_O1") (pintype "passive"))
    )
    (net (code "191") (name "unconnected-(K1C-O-PadO2)") (class "Default")
      (node (ref "K1") (pin "O2") (pinfunction "O_O2") (pintype "passive"))
    )
    (net (code "192") (name "unconnected-(K1C-S-PadS2)") (class "Default")
      (node (ref "K1") (pin "S2") (pinfunction "S_S2") (pintype "passive"))
    )
    (net (code "193") (name "unconnected-(K2B-O-PadO1)") (class "Default")
      (node (ref "K2") (pin "O1") (pinfunction "O_O1") (pintype "passive"))
    )
    (net (code "194") (name "unconnected-(K2C-O-PadO2)") (class "Default")
      (node (ref "K2") (pin "O2") (pinfunction "O_O2") (pintype "passive"))
    )
    (net (code "195") (name "unconnected-(K2C-S-PadS2)") (class "Default")
      (node (ref "K2") (pin "S2") (pinfunction "S_S2") (pintype "passive"))
    )
    (net (code "196") (name "unconnected-(K3B-O-PadO1)") (class "Default")
      (node (ref "K3") (pin "O1") (pinfunction "O_O1") (pintype "passive"))
    )
    (net (code "197") (name "unconnected-(K3C-O-PadO2)") (class "Default")
      (node (ref "K3") (pin "O2") (pinfunction "O_O2") (pintype "passive"))
    )
    (net (code "198") (name "unconnected-(K3C-S-PadS2)") (class "Default")
      (node (ref "K3") (pin "S2") (pinfunction "S_S2") (pintype "passive"))
    )
    (net (code "199") (name "unconnected-(K4B-O-PadO1)") (class "Default")
      (node (ref "K4") (pin "O1") (pinfunction "O_O1") (pintype "passive"))
    )
    (net (code "200") (name "unconnected-(K4C-O-PadO2)") (class "Default")
      (node (ref "K4") (pin "O2") (pinfunction "O_O2") (pintype "passive"))
    )
    (net (code "201") (name "unconnected-(K4C-S-PadS2)") (class "Default")
      (node (ref "K4") (pin "S2") (pinfunction "S_S2") (pintype "passive"))
    )
    (net (code "202") (name "unconnected-(K5B-O-PadO1)") (class "Default")
      (node (ref "K5") (pin "O1") (pinfunction "O_O1") (pintype "passive"))
    )
    (net (code "203") (name "unconnected-(K5C-O-PadO2)") (class "Default")
      (node (ref "K5") (pin "O2") (pinfunction "O_O2") (pintype "passive"))
    )
    (net (code "204") (name "unconnected-(K5C-S-PadS2)") (class "Default")
      (node (ref "K5") (pin "S2") (pinfunction "S_S2") (pintype "passive"))
    )
    (net (code "205") (name "unconnected-(K6B-O-PadO1)") (class "Default")
      (node (ref "K6") (pin "O1") (pinfunction "O_O1") (pintype "passive"))
    )
    (net (code "206") (name "unconnected-(K6C-O-PadO2)") (class "Default")
      (node (ref "K6") (pin "O2") (pinfunction "O_O2") (pintype "passive"))
    )
    (net (code "207") (name "unconnected-(K6C-S-PadS2)") (class "Default")
      (node (ref "K6") (pin "S2") (pinfunction "S_S2") (pintype "passive"))
    )
    (net (code "208") (name "unconnected-(K7B-O-PadO1)") (class "Default")
      (node (ref "K7") (pin "O1") (pinfunction "O_O1") (pintype "passive"))
    )
    (net (code "209") (name "unconnected-(K7C-O-PadO2)") (class "Default")
      (node (ref "K7") (pin "O2") (pinfunction "O_O2") (pintype "passive"))
    )
    (net (code "210") (name "unconnected-(K7C-S-PadS2)") (class "Default")
      (node (ref "K7") (pin "S2") (pinfunction "S_S2") (pintype "passive"))
    )
    (net (code "211") (name "unconnected-(K8B-O-PadO1)") (class "Default")
      (node (ref "K8") (pin "O1") (pinfunction "O_O1") (pintype "passive"))
    )
    (net (code "212") (name "unconnected-(K8C-O-PadO2)") (class "Default")
      (node (ref "K8") (pin "O2") (pinfunction "O_O2") (pintype "passive"))
    )
    (net (code "213") (name "unconnected-(K8C-S-PadS2)") (class "Default")
      (node (ref "K8") (pin "S2") (pinfunction "S_S2") (pintype "passive"))
    )
  )
)
